# PSU.net
KiCad netlist of a schematic drawn in EAGLE
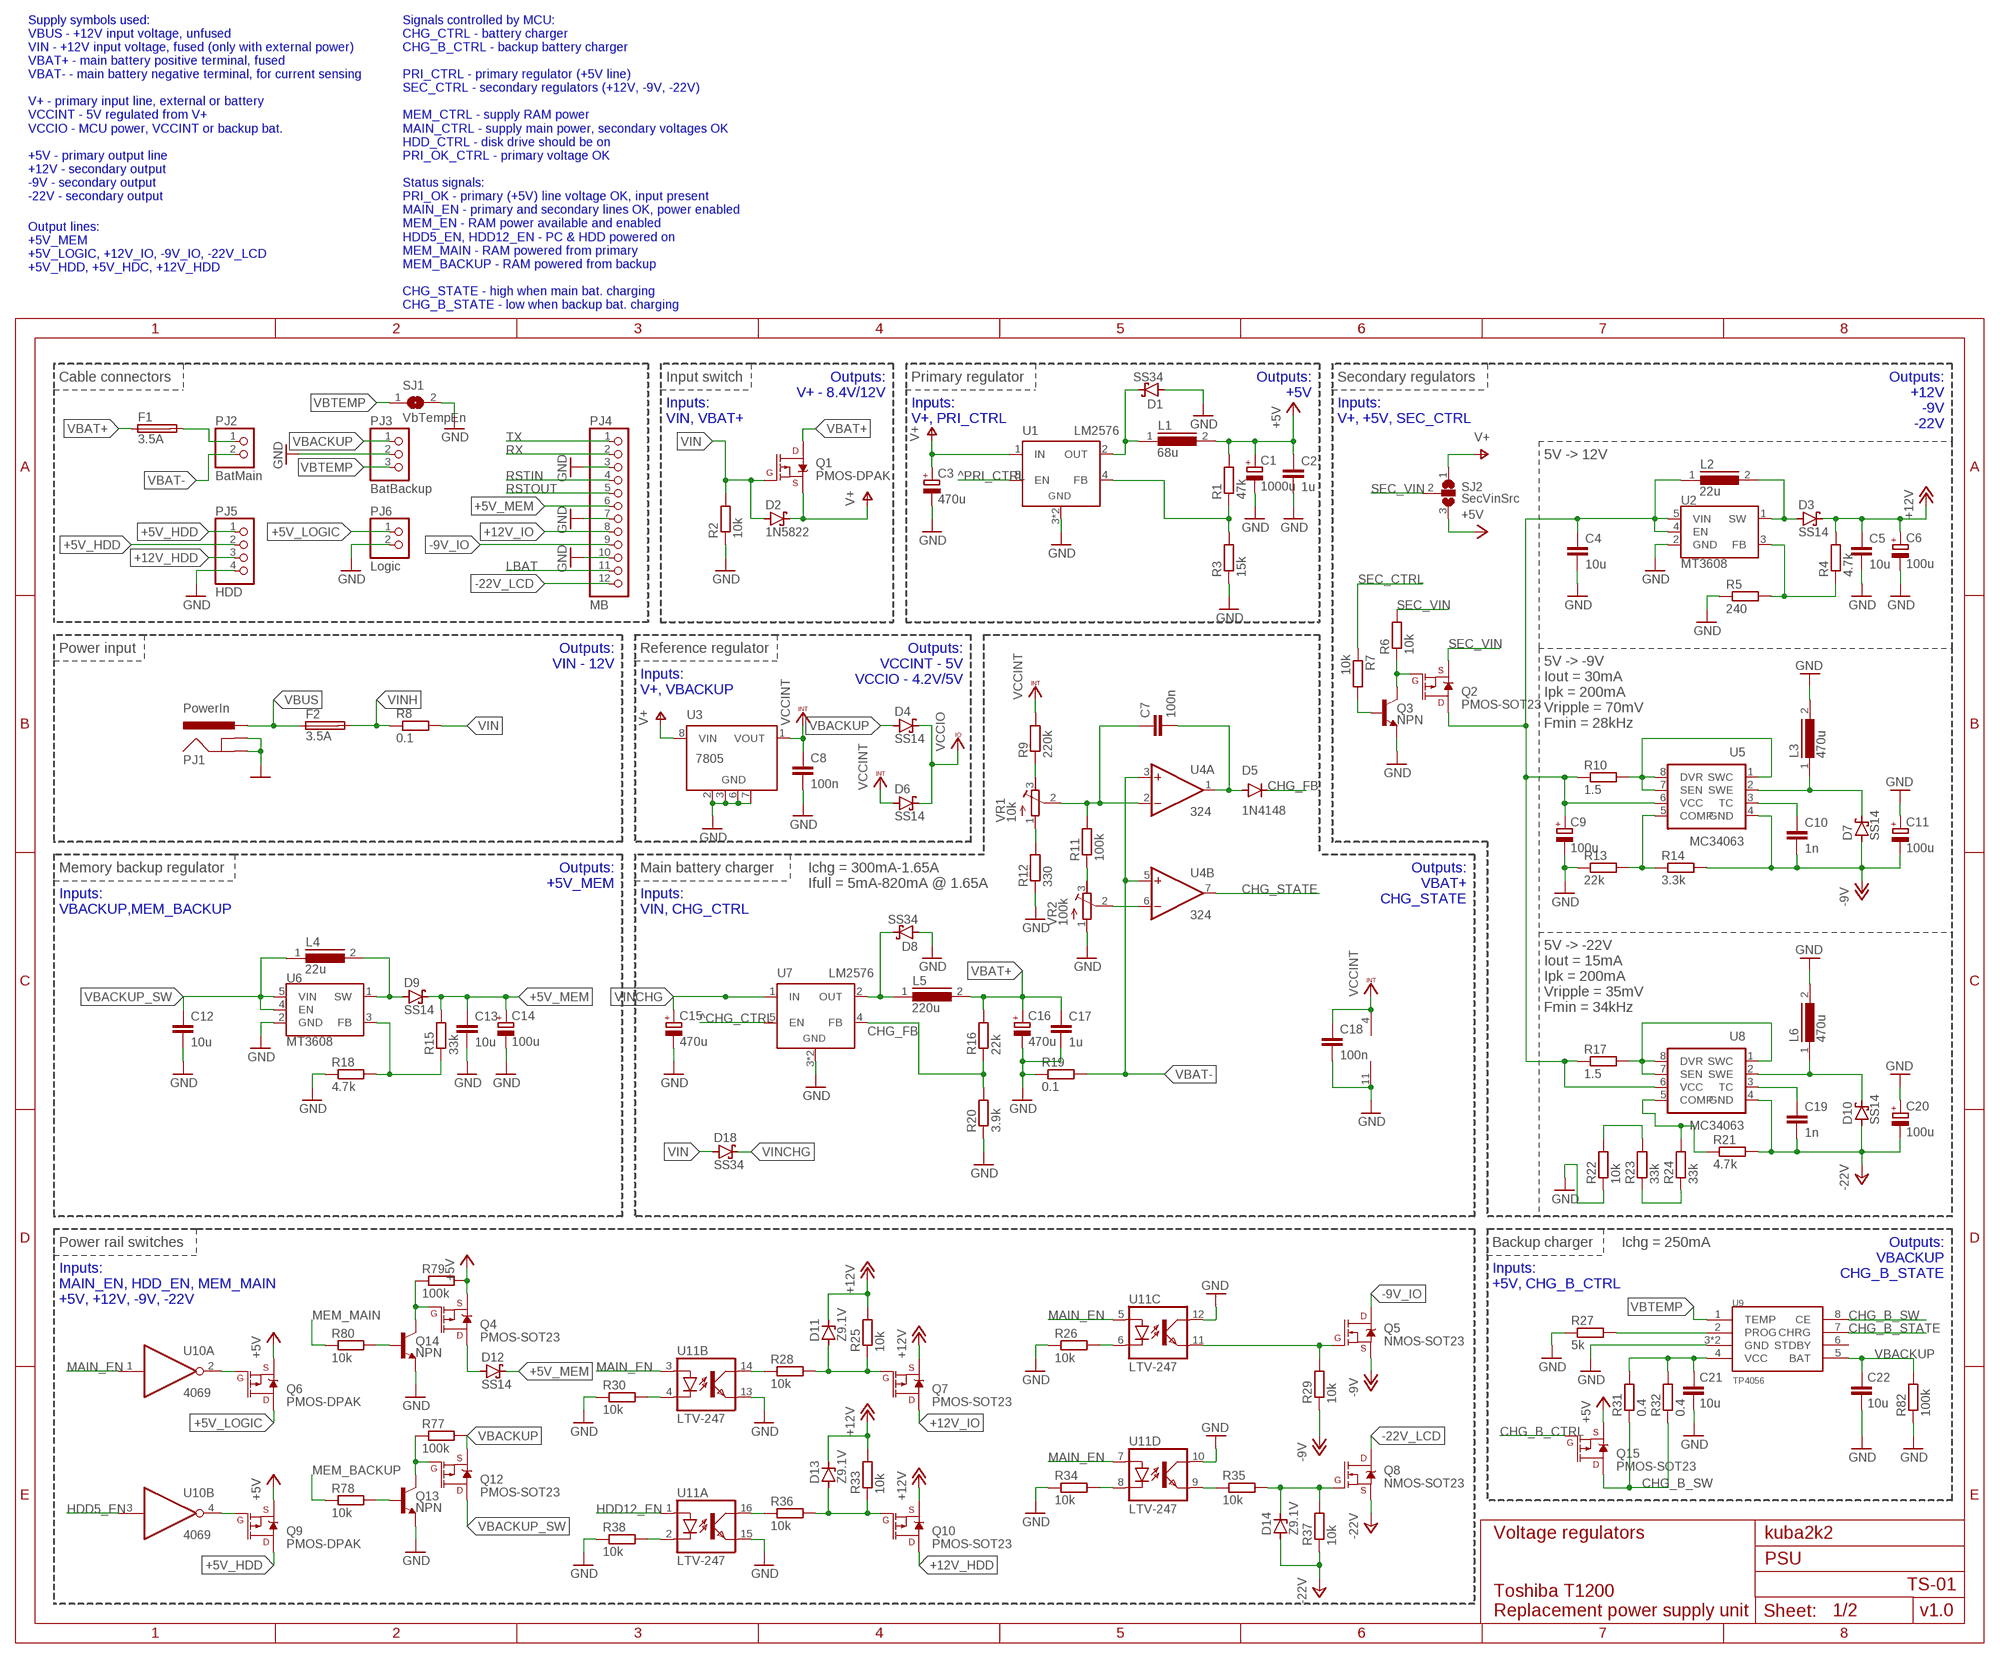
[diagram p0: schematic, sheet 1]
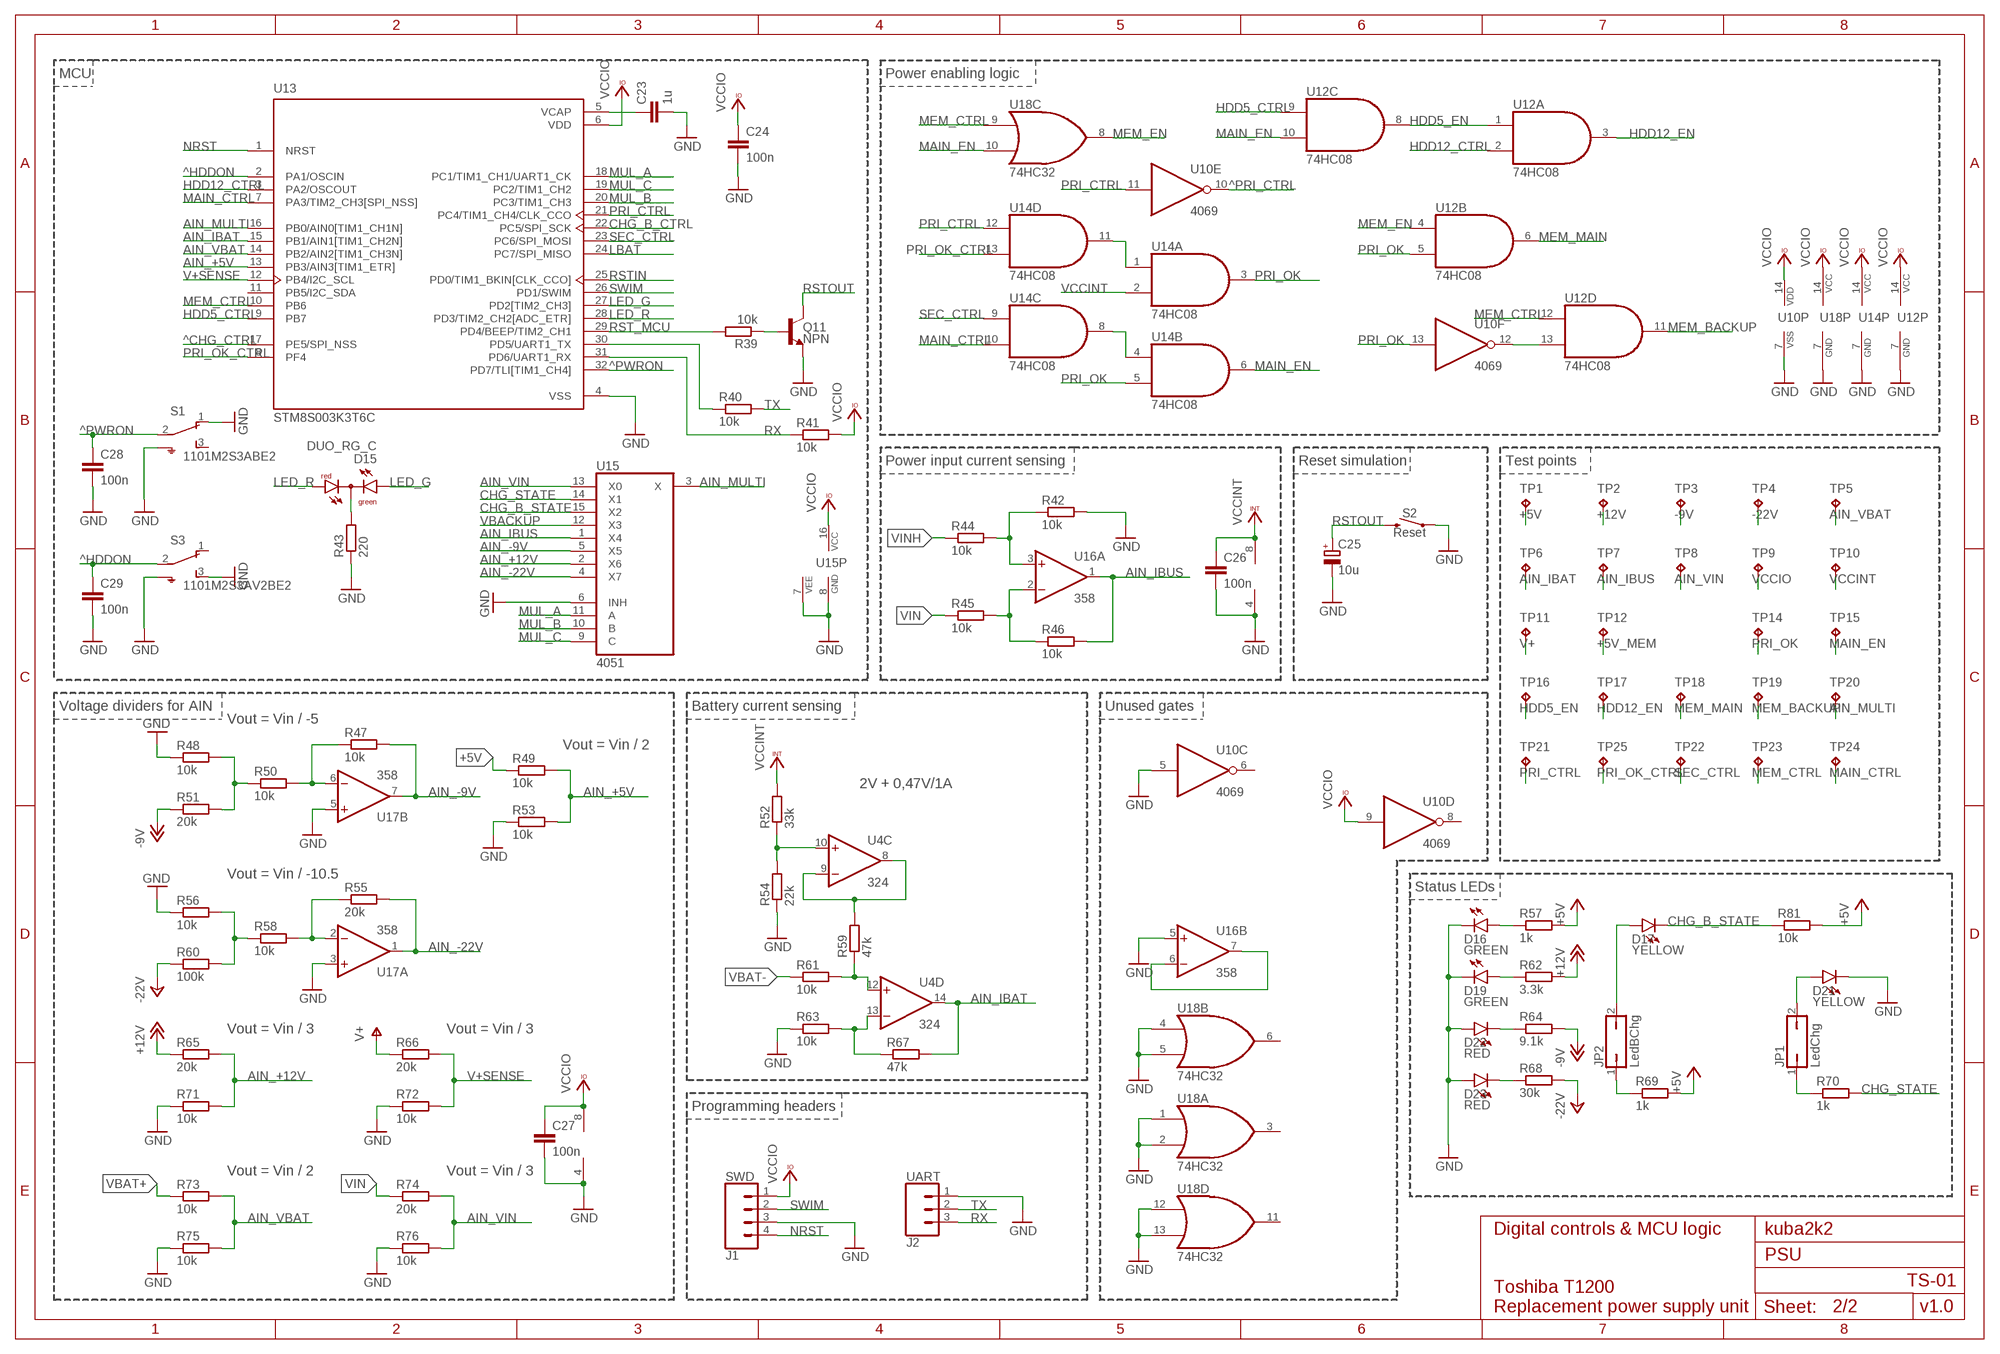
[diagram p1: schematic, sheet 2]

(export (version "E")
  (design (tool "Eeschema 10.0.6"))
  (components
    (comp (ref "C1")
      (value "1000u")
      (footprint "eagle-import:E5-10,5")
      (libsource (lib "eagle-import") (part "CPOL-EUE5-10.5"))
    )
    (comp (ref "C2")
      (value "1u")
      (footprint "eagle-import:C050-024X044")
      (libsource (lib "eagle-import") (part "C-EU050-024X044"))
    )
    (comp (ref "C3")
      (value "470u")
      (footprint "eagle-import:E3,5-8")
      (libsource (lib "eagle-import") (part "CPOL-EUE3.5-8"))
    )
    (comp (ref "C4")
      (value "10u")
      (footprint "eagle-import:C1206")
      (libsource (lib "eagle-import") (part "C-EUC1206"))
    )
    (comp (ref "C5")
      (value "10u")
      (footprint "eagle-import:C1206")
      (libsource (lib "eagle-import") (part "C-EUC1206"))
    )
    (comp (ref "C6")
      (value "100u")
      (footprint "eagle-import:E3,5-8")
      (libsource (lib "eagle-import") (part "CPOL-EUE3.5-8"))
    )
    (comp (ref "C7")
      (value "100n")
      (footprint "eagle-import:C0805")
      (libsource (lib "eagle-import") (part "C-EUC0805"))
    )
    (comp (ref "C8")
      (value "100n")
      (footprint "eagle-import:C0805")
      (libsource (lib "eagle-import") (part "C-EUC0805"))
    )
    (comp (ref "C9")
      (value "100u")
      (footprint "eagle-import:E3,5-8")
      (libsource (lib "eagle-import") (part "CPOL-EUE3.5-8"))
    )
    (comp (ref "C10")
      (value "1n")
      (footprint "eagle-import:C0805")
      (libsource (lib "eagle-import") (part "C-EUC0805"))
    )
    (comp (ref "C11")
      (value "100u")
      (footprint "eagle-import:E3,5-8")
      (libsource (lib "eagle-import") (part "CPOL-EUE3.5-8"))
    )
    (comp (ref "C12")
      (value "10u")
      (footprint "eagle-import:C1206")
      (libsource (lib "eagle-import") (part "C-EUC1206"))
    )
    (comp (ref "C13")
      (value "10u")
      (footprint "eagle-import:C1206")
      (libsource (lib "eagle-import") (part "C-EUC1206"))
    )
    (comp (ref "C14")
      (value "100u")
      (footprint "eagle-import:E3,5-8")
      (libsource (lib "eagle-import") (part "CPOL-EUE3.5-8"))
    )
    (comp (ref "C15")
      (value "470u")
      (footprint "eagle-import:E3,5-8")
      (libsource (lib "eagle-import") (part "CPOL-EUE3.5-8"))
    )
    (comp (ref "C16")
      (value "470u")
      (footprint "eagle-import:E3,5-8")
      (libsource (lib "eagle-import") (part "CPOL-EUE3.5-8"))
    )
    (comp (ref "C17")
      (value "1u")
      (footprint "eagle-import:C050-024X044")
      (libsource (lib "eagle-import") (part "C-EU050-024X044"))
    )
    (comp (ref "C18")
      (value "100n")
      (footprint "eagle-import:C0805")
      (libsource (lib "eagle-import") (part "C-EUC0805"))
    )
    (comp (ref "C19")
      (value "1n")
      (footprint "eagle-import:C0805")
      (libsource (lib "eagle-import") (part "C-EUC0805"))
    )
    (comp (ref "C20")
      (value "100u")
      (footprint "eagle-import:E3,5-8")
      (libsource (lib "eagle-import") (part "CPOL-EUE3.5-8"))
    )
    (comp (ref "C21")
      (value "10u")
      (footprint "eagle-import:C1206")
      (libsource (lib "eagle-import") (part "C-EUC1206"))
    )
    (comp (ref "C22")
      (value "10u")
      (footprint "eagle-import:C1206")
      (libsource (lib "eagle-import") (part "C-EUC1206"))
    )
    (comp (ref "D1")
      (value "SS34")
      (footprint "eagle-import:SMC")
      (libsource (lib "eagle-import") (part "SS34"))
    )
    (comp (ref "D2")
      (value "1N5822")
      (footprint "eagle-import:F126Z12")
      (libsource (lib "eagle-import") (part "SCHOTTKY-DIODEF126Z12"))
    )
    (comp (ref "D3")
      (value "SS14")
      (footprint "eagle-import:DO-214AC")
      (libsource (lib "eagle-import") (part "SS14"))
    )
    (comp (ref "D4")
      (value "SS14")
      (footprint "eagle-import:DO-214AC")
      (libsource (lib "eagle-import") (part "SS14"))
    )
    (comp (ref "D5")
      (value "1N4148")
      (footprint "eagle-import:DO35-7")
      (libsource (lib "eagle-import") (part "1N4148DO35-7"))
    )
    (comp (ref "D6")
      (value "SS14")
      (footprint "eagle-import:DO-214AC")
      (libsource (lib "eagle-import") (part "SS14"))
    )
    (comp (ref "D7")
      (value "SS14")
      (footprint "eagle-import:DO-214AC")
      (libsource (lib "eagle-import") (part "SS14"))
    )
    (comp (ref "D8")
      (value "SS34")
      (footprint "eagle-import:SMC")
      (libsource (lib "eagle-import") (part "SS34"))
    )
    (comp (ref "D9")
      (value "SS14")
      (footprint "eagle-import:DO-214AC")
      (libsource (lib "eagle-import") (part "SS14"))
    )
    (comp (ref "D10")
      (value "SS14")
      (footprint "eagle-import:DO-214AC")
      (libsource (lib "eagle-import") (part "SS14"))
    )
    (comp (ref "D11")
      (value "Z9.1V")
      (footprint "eagle-import:DO34Z7")
      (libsource (lib "eagle-import") (part "ZENER-DIODEDO34-7"))
    )
    (comp (ref "D12")
      (value "SS14")
      (footprint "eagle-import:DO-214AC")
      (libsource (lib "eagle-import") (part "SS14"))
    )
    (comp (ref "D13")
      (value "Z9.1V")
      (footprint "eagle-import:DO34Z7")
      (libsource (lib "eagle-import") (part "ZENER-DIODEDO34-7"))
    )
    (comp (ref "D14")
      (value "Z9.1V")
      (footprint "eagle-import:DO34Z7")
      (libsource (lib "eagle-import") (part "ZENER-DIODEDO34-7"))
    )
    (comp (ref "D18")
      (value "SS34")
      (footprint "eagle-import:SMC")
      (libsource (lib "eagle-import") (part "SS34"))
    )
    (comp (ref "F1")
      (value "3.5A")
      (footprint "eagle-import:2512")
      (libsource (lib "eagle-import") (part "FUSE-2512"))
    )
    (comp (ref "F2")
      (value "3.5A")
      (footprint "eagle-import:2512")
      (libsource (lib "eagle-import") (part "FUSE-2512"))
    )
    (comp (ref "L1")
      (value "68u")
      (footprint "eagle-import:SFT1030")
      (libsource (lib "eagle-import") (part "SFT1030"))
    )
    (comp (ref "L2")
      (value "22u")
      (footprint "eagle-import:DR127")
      (libsource (lib "eagle-import") (part "DR127"))
    )
    (comp (ref "L3")
      (value "470u")
      (footprint "eagle-import:COIL0608")
      (libsource (lib "eagle-import") (part "COIL0608"))
    )
    (comp (ref "L4")
      (value "22u")
      (footprint "eagle-import:DR127")
      (libsource (lib "eagle-import") (part "DR127"))
    )
    (comp (ref "L5")
      (value "220u")
      (footprint "eagle-import:SFT1030")
      (libsource (lib "eagle-import") (part "SFT1030"))
    )
    (comp (ref "L6")
      (value "470u")
      (footprint "eagle-import:COIL0608")
      (libsource (lib "eagle-import") (part "COIL0608"))
    )
    (comp (ref "PJ1")
      (value "PowerIn")
      (footprint "eagle-import:POWER_JACK_PTH")
      (libsource (lib "eagle-import") (part "POWER_JACK"))
    )
    (comp (ref "PJ2")
      (value "BatMain")
      (footprint "eagle-import:JST-PH2-4.00")
      (libsource (lib "eagle-import") (part "JST-PH2-4.00"))
    )
    (comp (ref "PJ3")
      (value "BatBackup")
      (footprint "eagle-import:JST-PH3")
      (libsource (lib "eagle-import") (part "JST-PH3"))
    )
    (comp (ref "PJ4")
      (value "MB")
      (footprint "eagle-import:JST-PH12")
      (libsource (lib "eagle-import") (part "JST-PH12"))
    )
    (comp (ref "PJ5")
      (value "HDD")
      (footprint "eagle-import:JST-PH4-2.54")
      (libsource (lib "eagle-import") (part "JST-PH4-2.54"))
    )
    (comp (ref "PJ6")
      (value "Logic")
      (footprint "eagle-import:JST-PH2-2.54")
      (libsource (lib "eagle-import") (part "JST-PH2-2.54"))
    )
    (comp (ref "Q1")
      (value "PMOS-DPAK")
      (footprint "eagle-import:TO-252_DPAK")
      (libsource (lib "eagle-import") (part "MOSFET_PCH-MCU20P10"))
    )
    (comp (ref "Q2")
      (value "PMOS-SOT23")
      (footprint "eagle-import:SOT23-3")
      (libsource (lib "eagle-import") (part "MOSFET_PCH-IRLML2244"))
    )
    (comp (ref "Q3")
      (value "NPN")
      (footprint "eagle-import:SOT23-3")
      (libsource (lib "eagle-import") (part "TRANS_NPN-MMBT2222AL"))
    )
    (comp (ref "Q4")
      (value "PMOS-SOT23")
      (footprint "eagle-import:SOT23-3")
      (libsource (lib "eagle-import") (part "MOSFET_PCH-IRLML2244"))
    )
    (comp (ref "Q5")
      (value "NMOS-SOT23")
      (footprint "eagle-import:SOT23-3")
      (libsource (lib "eagle-import") (part "MOSFET-NCH-AO3404A"))
    )
    (comp (ref "Q6")
      (value "PMOS-DPAK")
      (footprint "eagle-import:TO-252_DPAK")
      (libsource (lib "eagle-import") (part "MOSFET_PCH-MCU20P10"))
    )
    (comp (ref "Q7")
      (value "PMOS-SOT23")
      (footprint "eagle-import:SOT23-3")
      (libsource (lib "eagle-import") (part "MOSFET_PCH-IRLML2244"))
    )
    (comp (ref "Q8")
      (value "NMOS-SOT23")
      (footprint "eagle-import:SOT23-3")
      (libsource (lib "eagle-import") (part "MOSFET-NCH-AO3404A"))
    )
    (comp (ref "Q9")
      (value "PMOS-DPAK")
      (footprint "eagle-import:TO-252_DPAK")
      (libsource (lib "eagle-import") (part "MOSFET_PCH-MCU20P10"))
    )
    (comp (ref "Q10")
      (value "PMOS-SOT23")
      (footprint "eagle-import:SOT23-3")
      (libsource (lib "eagle-import") (part "MOSFET_PCH-IRLML2244"))
    )
    (comp (ref "Q12")
      (value "PMOS-SOT23")
      (footprint "eagle-import:SOT23-3")
      (libsource (lib "eagle-import") (part "MOSFET_PCH-IRLML2244"))
    )
    (comp (ref "Q13")
      (value "NPN")
      (footprint "eagle-import:SOT23-3")
      (libsource (lib "eagle-import") (part "TRANS_NPN-MMBT2222AL"))
    )
    (comp (ref "Q14")
      (value "NPN")
      (footprint "eagle-import:SOT23-3")
      (libsource (lib "eagle-import") (part "TRANS_NPN-MMBT2222AL"))
    )
    (comp (ref "Q15")
      (value "PMOS-SOT23")
      (footprint "eagle-import:SOT23-3")
      (libsource (lib "eagle-import") (part "MOSFET_PCH-IRLML2244"))
    )
    (comp (ref "R1")
      (value "47k")
      (footprint "eagle-import:R0805")
      (libsource (lib "eagle-import") (part "R-EU_R0805"))
    )
    (comp (ref "R2")
      (value "10k")
      (footprint "eagle-import:R0805")
      (libsource (lib "eagle-import") (part "R-EU_R0805"))
    )
    (comp (ref "R3")
      (value "15k")
      (footprint "eagle-import:R0805")
      (libsource (lib "eagle-import") (part "R-EU_R0805"))
    )
    (comp (ref "R4")
      (value "4.7k")
      (footprint "eagle-import:R0805")
      (libsource (lib "eagle-import") (part "R-EU_R0805"))
    )
    (comp (ref "R5")
      (value "240")
      (footprint "eagle-import:R0805")
      (libsource (lib "eagle-import") (part "R-EU_R0805"))
    )
    (comp (ref "R6")
      (value "10k")
      (footprint "eagle-import:R0805")
      (libsource (lib "eagle-import") (part "R-EU_R0805"))
    )
    (comp (ref "R7")
      (value "10k")
      (footprint "eagle-import:R0805")
      (libsource (lib "eagle-import") (part "R-EU_R0805"))
    )
    (comp (ref "R8")
      (value "0.1")
      (footprint "eagle-import:0411_15")
      (libsource (lib "eagle-import") (part "R-EU_0411/15"))
    )
    (comp (ref "R9")
      (value "220k")
      (footprint "eagle-import:R0805")
      (libsource (lib "eagle-import") (part "R-EU_R0805"))
    )
    (comp (ref "R10")
      (value "1.5")
      (footprint "eagle-import:0207_10")
      (libsource (lib "eagle-import") (part "R-EU_0207/10"))
    )
    (comp (ref "R11")
      (value "100k")
      (footprint "eagle-import:R0805")
      (libsource (lib "eagle-import") (part "R-EU_R0805"))
    )
    (comp (ref "R12")
      (value "330")
      (footprint "eagle-import:R0805")
      (libsource (lib "eagle-import") (part "R-EU_R0805"))
    )
    (comp (ref "R13")
      (value "22k")
      (footprint "eagle-import:R0805")
      (libsource (lib "eagle-import") (part "R-EU_R0805"))
    )
    (comp (ref "R14")
      (value "3.3k")
      (footprint "eagle-import:R0805")
      (libsource (lib "eagle-import") (part "R-EU_R0805"))
    )
    (comp (ref "R15")
      (value "33k")
      (footprint "eagle-import:R0805")
      (libsource (lib "eagle-import") (part "R-EU_R0805"))
    )
    (comp (ref "R16")
      (value "22k")
      (footprint "eagle-import:R0805")
      (libsource (lib "eagle-import") (part "R-EU_R0805"))
    )
    (comp (ref "R17")
      (value "1.5")
      (footprint "eagle-import:0207_10")
      (libsource (lib "eagle-import") (part "R-EU_0207/10"))
    )
    (comp (ref "R18")
      (value "4.7k")
      (footprint "eagle-import:R0805")
      (libsource (lib "eagle-import") (part "R-EU_R0805"))
    )
    (comp (ref "R19")
      (value "0.1")
      (footprint "eagle-import:0411_15")
      (libsource (lib "eagle-import") (part "R-EU_0411/15"))
    )
    (comp (ref "R20")
      (value "3.9k")
      (footprint "eagle-import:R0805")
      (libsource (lib "eagle-import") (part "R-EU_R0805"))
    )
    (comp (ref "R21")
      (value "4.7k")
      (footprint "eagle-import:R0805")
      (libsource (lib "eagle-import") (part "R-EU_R0805"))
    )
    (comp (ref "R22")
      (value "10k")
      (footprint "eagle-import:R0805")
      (libsource (lib "eagle-import") (part "R-EU_R0805"))
    )
    (comp (ref "R23")
      (value "33k")
      (footprint "eagle-import:R0805")
      (libsource (lib "eagle-import") (part "R-EU_R0805"))
    )
    (comp (ref "R24")
      (value "33k")
      (footprint "eagle-import:R0805")
      (libsource (lib "eagle-import") (part "R-EU_R0805"))
    )
    (comp (ref "R25")
      (value "10k")
      (footprint "eagle-import:R0805")
      (libsource (lib "eagle-import") (part "R-EU_R0805"))
    )
    (comp (ref "R26")
      (value "10k")
      (footprint "eagle-import:R0805")
      (libsource (lib "eagle-import") (part "R-EU_R0805"))
    )
    (comp (ref "R27")
      (value "5k")
      (footprint "eagle-import:R0805")
      (libsource (lib "eagle-import") (part "R-EU_R0805"))
    )
    (comp (ref "R28")
      (value "10k")
      (footprint "eagle-import:R0805")
      (libsource (lib "eagle-import") (part "R-EU_R0805"))
    )
    (comp (ref "R29")
      (value "10k")
      (footprint "eagle-import:R0805")
      (libsource (lib "eagle-import") (part "R-EU_R0805"))
    )
    (comp (ref "R30")
      (value "10k")
      (footprint "eagle-import:R0805")
      (libsource (lib "eagle-import") (part "R-EU_R0805"))
    )
    (comp (ref "R31")
      (value "0.4")
      (footprint "eagle-import:0207_10")
      (libsource (lib "eagle-import") (part "R-EU_0207/10"))
    )
    (comp (ref "R32")
      (value "0.4")
      (footprint "eagle-import:R1206")
      (libsource (lib "eagle-import") (part "R-EU_R1206"))
    )
    (comp (ref "R33")
      (value "10k")
      (footprint "eagle-import:R0805")
      (libsource (lib "eagle-import") (part "R-EU_R0805"))
    )
    (comp (ref "R34")
      (value "10k")
      (footprint "eagle-import:R0805")
      (libsource (lib "eagle-import") (part "R-EU_R0805"))
    )
    (comp (ref "R35")
      (value "10k")
      (footprint "eagle-import:R0805")
      (libsource (lib "eagle-import") (part "R-EU_R0805"))
    )
    (comp (ref "R36")
      (value "10k")
      (footprint "eagle-import:R0805")
      (libsource (lib "eagle-import") (part "R-EU_R0805"))
    )
    (comp (ref "R37")
      (value "10k")
      (footprint "eagle-import:R0805")
      (libsource (lib "eagle-import") (part "R-EU_R0805"))
    )
    (comp (ref "R38")
      (value "10k")
      (footprint "eagle-import:R0805")
      (libsource (lib "eagle-import") (part "R-EU_R0805"))
    )
    (comp (ref "R77")
      (value "100k")
      (footprint "eagle-import:R0805")
      (libsource (lib "eagle-import") (part "R-EU_R0805"))
    )
    (comp (ref "R78")
      (value "10k")
      (footprint "eagle-import:R0805")
      (libsource (lib "eagle-import") (part "R-EU_R0805"))
    )
    (comp (ref "R79")
      (value "100k")
      (footprint "eagle-import:R0805")
      (libsource (lib "eagle-import") (part "R-EU_R0805"))
    )
    (comp (ref "R80")
      (value "10k")
      (footprint "eagle-import:R0805")
      (libsource (lib "eagle-import") (part "R-EU_R0805"))
    )
    (comp (ref "R82")
      (value "100k")
      (footprint "eagle-import:R0805")
      (libsource (lib "eagle-import") (part "R-EU_R0805"))
    )
    (comp (ref "SJ1")
      (value "VbTempEn")
      (footprint "eagle-import:SJ")
      (libsource (lib "eagle-import") (part "SJ"))
    )
    (comp (ref "SJ2")
      (value "SecVinSrc")
      (footprint "eagle-import:SJ_2")
      (libsource (lib "eagle-import") (part "SJ2W"))
    )
    (comp (ref "U1")
      (value "LM2576")
      (footprint "eagle-import:TO220-52-VIAHOLE")
      (fields (field (name "SPICEPREFIX") "X"))
      (libsource (lib "eagle-import") (part "LM2596TH-VIAHOLE"))
    )
    (comp (ref "U2")
      (value "MT3608")
      (footprint "eagle-import:SOT23-6")
      (fields (field (name "SPICEPREFIX") "X"))
      (libsource (lib "eagle-import") (part "MT3608"))
    )
    (comp (ref "U3")
      (value "7805")
      (footprint "eagle-import:SO08")
      (libsource (lib "eagle-import") (part "78LSMD05"))
    )
    (comp (ref "U4")
      (value "324")
      (footprint "eagle-import:SO14")
      (libsource (lib "eagle-import") (part "LM324D"))
    )
    (comp (ref "U5")
      (value "MC34063")
      (footprint "eagle-import:SO08")
      (libsource (lib "eagle-import") (part "MC34063SMD"))
    )
    (comp (ref "U6")
      (value "MT3608")
      (footprint "eagle-import:SOT23-6")
      (libsource (lib "eagle-import") (part "MT3608"))
    )
    (comp (ref "U7")
      (value "LM2576")
      (footprint "eagle-import:TO220-52-VIAHOLE")
      (libsource (lib "eagle-import") (part "LM2596TH-VIAHOLE"))
    )
    (comp (ref "U8")
      (value "MC34063")
      (footprint "eagle-import:SO08")
      (libsource (lib "eagle-import") (part "MC34063SMD"))
    )
    (comp (ref "U9")
      (value "TP4056")
      (footprint "eagle-import:SO08-PAD")
      (libsource (lib "eagle-import") (part "TP4056"))
    )
    (comp (ref "U10")
      (value "4069")
      (footprint "eagle-import:SO14")
      (libsource (lib "eagle-import") (part "4069D"))
    )
    (comp (ref "U11")
      (value "LTV-247")
      (footprint "eagle-import:SO16-GULLWING")
      (libsource (lib "eagle-import") (part "LTV-247"))
    )
    (comp (ref "VR1")
      (value "10k")
      (footprint "eagle-import:RTRIM3296W")
      (libsource (lib "eagle-import") (part "R-TRIMM3296W"))
    )
    (comp (ref "VR2")
      (value "100k")
      (footprint "eagle-import:RTRIM3296W")
      (libsource (lib "eagle-import") (part "R-TRIMM3296W"))
    )
    (comp (ref "C23")
      (value "1u")
      (footprint "eagle-import:C050-024X044")
      (libsource (lib "eagle-import") (part "C-EU050-024X044"))
    )
    (comp (ref "C24")
      (value "100n")
      (footprint "eagle-import:C0805")
      (libsource (lib "eagle-import") (part "C-EUC0805"))
    )
    (comp (ref "C25")
      (value "10u")
      (footprint "eagle-import:E2-5")
      (libsource (lib "eagle-import") (part "CPOL-EUE2-5"))
    )
    (comp (ref "C26")
      (value "100n")
      (footprint "eagle-import:C0805")
      (libsource (lib "eagle-import") (part "C-EUC0805"))
    )
    (comp (ref "C27")
      (value "100n")
      (footprint "eagle-import:C0805")
      (libsource (lib "eagle-import") (part "C-EUC0805"))
    )
    (comp (ref "C28")
      (value "100n")
      (footprint "eagle-import:C0805")
      (libsource (lib "eagle-import") (part "C-EUC0805"))
    )
    (comp (ref "C29")
      (value "100n")
      (footprint "eagle-import:C0805")
      (libsource (lib "eagle-import") (part "C-EUC0805"))
    )
    (comp (ref "D15")
      (value "DUO_RG_C")
      (footprint "eagle-import:DUOLED-C-5MM")
      (libsource (lib "eagle-import") (part "DUOLED-RG-C"))
    )
    (comp (ref "D16")
      (value "GREEN")
      (footprint "eagle-import:CHIP-LED0805")
      (libsource (lib "eagle-import") (part "LEDCHIP-LED0805"))
    )
    (comp (ref "D17")
      (value "YELLOW")
      (footprint "eagle-import:CHIP-LED0805")
      (libsource (lib "eagle-import") (part "LEDCHIP-LED0805"))
    )
    (comp (ref "D19")
      (value "GREEN")
      (footprint "eagle-import:CHIP-LED0805")
      (libsource (lib "eagle-import") (part "LEDCHIP-LED0805"))
    )
    (comp (ref "D21")
      (value "YELLOW")
      (footprint "eagle-import:CHIP-LED0805")
      (libsource (lib "eagle-import") (part "LEDCHIP-LED0805"))
    )
    (comp (ref "D22")
      (value "RED")
      (footprint "eagle-import:CHIP-LED0805")
      (libsource (lib "eagle-import") (part "LEDCHIP-LED0805"))
    )
    (comp (ref "D23")
      (value "RED")
      (footprint "eagle-import:CHIP-LED0805")
      (libsource (lib "eagle-import") (part "LEDCHIP-LED0805"))
    )
    (comp (ref "J1")
      (value "SWD")
      (footprint "eagle-import:1X04")
      (libsource (lib "eagle-import") (part "CONN_04PTH"))
    )
    (comp (ref "J2")
      (value "UART")
      (footprint "eagle-import:1X03")
      (libsource (lib "eagle-import") (part "CONN_03"))
    )
    (comp (ref "JP1")
      (value "LedChg")
      (footprint "eagle-import:JP1")
      (libsource (lib "eagle-import") (part "JP1Q"))
    )
    (comp (ref "JP2")
      (value "LedBChg")
      (footprint "eagle-import:JP1")
      (libsource (lib "eagle-import") (part "JP1Q"))
    )
    (comp (ref "Q11")
      (value "NPN")
      (footprint "eagle-import:SOT23-3")
      (libsource (lib "eagle-import") (part "TRANS_NPN-MMBT2222AL"))
    )
    (comp (ref "R39")
      (value "10k")
      (footprint "eagle-import:R0805")
      (libsource (lib "eagle-import") (part "R-EU_R0805"))
    )
    (comp (ref "R40")
      (value "10k")
      (footprint "eagle-import:R0805")
      (libsource (lib "eagle-import") (part "R-EU_R0805"))
    )
    (comp (ref "R41")
      (value "10k")
      (footprint "eagle-import:R0805")
      (libsource (lib "eagle-import") (part "R-EU_R0805"))
    )
    (comp (ref "R42")
      (value "10k")
      (footprint "eagle-import:R0805")
      (libsource (lib "eagle-import") (part "R-EU_R0805"))
    )
    (comp (ref "R43")
      (value "220")
      (footprint "eagle-import:R0805")
      (libsource (lib "eagle-import") (part "R-EU_R0805"))
    )
    (comp (ref "R44")
      (value "10k")
      (footprint "eagle-import:R0805")
      (libsource (lib "eagle-import") (part "R-EU_R0805"))
    )
    (comp (ref "R45")
      (value "10k")
      (footprint "eagle-import:R0805")
      (libsource (lib "eagle-import") (part "R-EU_R0805"))
    )
    (comp (ref "R46")
      (value "10k")
      (footprint "eagle-import:R0805")
      (libsource (lib "eagle-import") (part "R-EU_R0805"))
    )
    (comp (ref "R47")
      (value "10k")
      (footprint "eagle-import:R0805")
      (libsource (lib "eagle-import") (part "R-EU_R0805"))
    )
    (comp (ref "R48")
      (value "10k")
      (footprint "eagle-import:R0805")
      (libsource (lib "eagle-import") (part "R-EU_R0805"))
    )
    (comp (ref "R49")
      (value "10k")
      (footprint "eagle-import:R0805")
      (libsource (lib "eagle-import") (part "R-EU_R0805"))
    )
    (comp (ref "R50")
      (value "10k")
      (footprint "eagle-import:R0805")
      (libsource (lib "eagle-import") (part "R-EU_R0805"))
    )
    (comp (ref "R51")
      (value "20k")
      (footprint "eagle-import:R0805")
      (libsource (lib "eagle-import") (part "R-EU_R0805"))
    )
    (comp (ref "R52")
      (value "33k")
      (footprint "eagle-import:R0805")
      (libsource (lib "eagle-import") (part "R-EU_R0805"))
    )
    (comp (ref "R53")
      (value "10k")
      (footprint "eagle-import:R0805")
      (libsource (lib "eagle-import") (part "R-EU_R0805"))
    )
    (comp (ref "R54")
      (value "22k")
      (footprint "eagle-import:R0805")
      (libsource (lib "eagle-import") (part "R-EU_R0805"))
    )
    (comp (ref "R55")
      (value "20k")
      (footprint "eagle-import:R0805")
      (libsource (lib "eagle-import") (part "R-EU_R0805"))
    )
    (comp (ref "R56")
      (value "10k")
      (footprint "eagle-import:R0805")
      (libsource (lib "eagle-import") (part "R-EU_R0805"))
    )
    (comp (ref "R57")
      (value "1k")
      (footprint "eagle-import:R0805")
      (libsource (lib "eagle-import") (part "R-EU_R0805"))
    )
    (comp (ref "R58")
      (value "10k")
      (footprint "eagle-import:R0805")
      (libsource (lib "eagle-import") (part "R-EU_R0805"))
    )
    (comp (ref "R59")
      (value "47k")
      (footprint "eagle-import:R0805")
      (libsource (lib "eagle-import") (part "R-EU_R0805"))
    )
    (comp (ref "R60")
      (value "100k")
      (footprint "eagle-import:R0805")
      (libsource (lib "eagle-import") (part "R-EU_R0805"))
    )
    (comp (ref "R61")
      (value "10k")
      (footprint "eagle-import:R0805")
      (libsource (lib "eagle-import") (part "R-EU_R0805"))
    )
    (comp (ref "R62")
      (value "3.3k")
      (footprint "eagle-import:R0805")
      (libsource (lib "eagle-import") (part "R-EU_R0805"))
    )
    (comp (ref "R63")
      (value "10k")
      (footprint "eagle-import:R0805")
      (libsource (lib "eagle-import") (part "R-EU_R0805"))
    )
    (comp (ref "R64")
      (value "9.1k")
      (footprint "eagle-import:R0805")
      (libsource (lib "eagle-import") (part "R-EU_R0805"))
    )
    (comp (ref "R65")
      (value "20k")
      (footprint "eagle-import:R0805")
      (libsource (lib "eagle-import") (part "R-EU_R0805"))
    )
    (comp (ref "R66")
      (value "20k")
      (footprint "eagle-import:R0805")
      (libsource (lib "eagle-import") (part "R-EU_R0805"))
    )
    (comp (ref "R67")
      (value "47k")
      (footprint "eagle-import:R0805")
      (libsource (lib "eagle-import") (part "R-EU_R0805"))
    )
    (comp (ref "R68")
      (value "30k")
      (footprint "eagle-import:R0805")
      (libsource (lib "eagle-import") (part "R-EU_R0805"))
    )
    (comp (ref "R69")
      (value "1k")
      (footprint "eagle-import:R0805")
      (libsource (lib "eagle-import") (part "R-EU_R0805"))
    )
    (comp (ref "R70")
      (value "1k")
      (footprint "eagle-import:R0805")
      (libsource (lib "eagle-import") (part "R-EU_R0805"))
    )
    (comp (ref "R71")
      (value "10k")
      (footprint "eagle-import:R0805")
      (libsource (lib "eagle-import") (part "R-EU_R0805"))
    )
    (comp (ref "R72")
      (value "10k")
      (footprint "eagle-import:R0805")
      (libsource (lib "eagle-import") (part "R-EU_R0805"))
    )
    (comp (ref "R73")
      (value "10k")
      (footprint "eagle-import:R0805")
      (libsource (lib "eagle-import") (part "R-EU_R0805"))
    )
    (comp (ref "R74")
      (value "20k")
      (footprint "eagle-import:R0805")
      (libsource (lib "eagle-import") (part "R-EU_R0805"))
    )
    (comp (ref "R75")
      (value "10k")
      (footprint "eagle-import:R0805")
      (libsource (lib "eagle-import") (part "R-EU_R0805"))
    )
    (comp (ref "R76")
      (value "10k")
      (footprint "eagle-import:R0805")
      (libsource (lib "eagle-import") (part "R-EU_R0805"))
    )
    (comp (ref "R81")
      (value "10k")
      (footprint "eagle-import:R0805")
      (libsource (lib "eagle-import") (part "R-EU_R0805"))
    )
    (comp (ref "S1")
      (value "1101M2S3ABE2")
      (footprint "eagle-import:1101M2S3ABE2")
      (libsource (lib "eagle-import") (part "1101M2S3ABE2"))
    )
    (comp (ref "S2")
      (value "Reset")
      (footprint "eagle-import:TACTILE_SWITCH_SMD_6.2MM_TALL")
      (libsource (lib "eagle-import") (part "MOMENTARY-SWITCH-SPST-SMD-6.2MM-TALL"))
    )
    (comp (ref "S3")
      (value "1101M2S3AV2BE2")
      (footprint "eagle-import:1101M2S3AV2BE2")
      (libsource (lib "eagle-import") (part "1101M2S3AV2BE2"))
    )
    (comp (ref "TP1")
      (value "TPB1,27")
      (footprint "eagle-import:B1,27")
      (libsource (lib "eagle-import") (part "TPB1,27"))
    )
    (comp (ref "TP2")
      (value "TPB1,27")
      (footprint "eagle-import:B1,27")
      (libsource (lib "eagle-import") (part "TPB1,27"))
    )
    (comp (ref "TP3")
      (value "TPB1,27")
      (footprint "eagle-import:B1,27")
      (libsource (lib "eagle-import") (part "TPB1,27"))
    )
    (comp (ref "TP4")
      (value "TPB1,27")
      (footprint "eagle-import:B1,27")
      (libsource (lib "eagle-import") (part "TPB1,27"))
    )
    (comp (ref "TP5")
      (value "TPB1,27")
      (footprint "eagle-import:B1,27")
      (libsource (lib "eagle-import") (part "TPB1,27"))
    )
    (comp (ref "TP6")
      (value "TPB1,27")
      (footprint "eagle-import:B1,27")
      (libsource (lib "eagle-import") (part "TPB1,27"))
    )
    (comp (ref "TP7")
      (value "TPB1,27")
      (footprint "eagle-import:B1,27")
      (libsource (lib "eagle-import") (part "TPB1,27"))
    )
    (comp (ref "TP8")
      (value "TPB1,27")
      (footprint "eagle-import:B1,27")
      (libsource (lib "eagle-import") (part "TPB1,27"))
    )
    (comp (ref "TP9")
      (value "TPB1,27")
      (footprint "eagle-import:B1,27")
      (libsource (lib "eagle-import") (part "TPB1,27"))
    )
    (comp (ref "TP10")
      (value "TPB1,27")
      (footprint "eagle-import:B1,27")
      (libsource (lib "eagle-import") (part "TPB1,27"))
    )
    (comp (ref "TP11")
      (value "TPB1,27")
      (footprint "eagle-import:B1,27")
      (libsource (lib "eagle-import") (part "TPB1,27"))
    )
    (comp (ref "TP12")
      (value "TPB1,27")
      (footprint "eagle-import:B1,27")
      (libsource (lib "eagle-import") (part "TPB1,27"))
    )
    (comp (ref "TP14")
      (value "TPB1,27")
      (footprint "eagle-import:B1,27")
      (libsource (lib "eagle-import") (part "TPB1,27"))
    )
    (comp (ref "TP15")
      (value "TPB1,27")
      (footprint "eagle-import:B1,27")
      (libsource (lib "eagle-import") (part "TPB1,27"))
    )
    (comp (ref "TP16")
      (value "TPB1,27")
      (footprint "eagle-import:B1,27")
      (libsource (lib "eagle-import") (part "TPB1,27"))
    )
    (comp (ref "TP17")
      (value "TPB1,27")
      (footprint "eagle-import:B1,27")
      (libsource (lib "eagle-import") (part "TPB1,27"))
    )
    (comp (ref "TP18")
      (value "TPB1,27")
      (footprint "eagle-import:B1,27")
      (libsource (lib "eagle-import") (part "TPB1,27"))
    )
    (comp (ref "TP19")
      (value "TPB1,27")
      (footprint "eagle-import:B1,27")
      (libsource (lib "eagle-import") (part "TPB1,27"))
    )
    (comp (ref "TP20")
      (value "TPB1,27")
      (footprint "eagle-import:B1,27")
      (libsource (lib "eagle-import") (part "TPB1,27"))
    )
    (comp (ref "TP21")
      (value "TPB1,27")
      (footprint "eagle-import:B1,27")
      (libsource (lib "eagle-import") (part "TPB1,27"))
    )
    (comp (ref "TP22")
      (value "TPB1,27")
      (footprint "eagle-import:B1,27")
      (libsource (lib "eagle-import") (part "TPB1,27"))
    )
    (comp (ref "TP23")
      (value "TPB1,27")
      (footprint "eagle-import:B1,27")
      (libsource (lib "eagle-import") (part "TPB1,27"))
    )
    (comp (ref "TP24")
      (value "TPB1,27")
      (footprint "eagle-import:B1,27")
      (libsource (lib "eagle-import") (part "TPB1,27"))
    )
    (comp (ref "TP25")
      (value "TPB1,27")
      (footprint "eagle-import:B1,27")
      (libsource (lib "eagle-import") (part "TPB1,27"))
    )
    (comp (ref "U12")
      (value "74HC08")
      (footprint "eagle-import:SO14")
      (libsource (lib "eagle-import") (part "7408DLS"))
    )
    (comp (ref "U13")
      (value "STM8S003K3T6C")
      (footprint "eagle-import:QFP80P900X900X160-32N")
      (fields (field (name "MF") "STMicroelectronics"))
      (libsource (lib "eagle-import") (part "STM8S003K3T6C"))
    )
    (comp (ref "U14")
      (value "74HC08")
      (footprint "eagle-import:SO14")
      (libsource (lib "eagle-import") (part "7408DLS"))
    )
    (comp (ref "U15")
      (value "4051")
      (footprint "eagle-import:SO16")
      (libsource (lib "eagle-import") (part "4051D"))
    )
    (comp (ref "U16")
      (value "358")
      (footprint "eagle-import:SO08")
      (libsource (lib "eagle-import") (part "LM358D"))
    )
    (comp (ref "U17")
      (value "358")
      (footprint "eagle-import:SO08")
      (libsource (lib "eagle-import") (part "LM358D"))
    )
    (comp (ref "U18")
      (value "74HC32")
      (footprint "eagle-import:SO14")
      (libsource (lib "eagle-import") (part "7432D"))
    )
  )
  (nets
    (net (code "1") (name "+5V") (class "Default")
      (node (ref "C1") (pin "+") (pinfunction "+_+") (pintype "passive"))
      (node (ref "C2") (pin "1") (pinfunction "1_1") (pintype "passive"))
      (node (ref "L1") (pin "2") (pinfunction "2_2") (pintype "passive"))
      (node (ref "Q15") (pin "2") (pinfunction "S_2") (pintype "bidirectional"))
      (node (ref "Q4") (pin "2") (pinfunction "S_2") (pintype "bidirectional"))
      (node (ref "Q6") (pin "3") (pinfunction "S_3") (pintype "bidirectional"))
      (node (ref "Q9") (pin "3") (pinfunction "S_3") (pintype "bidirectional"))
      (node (ref "R1") (pin "2") (pinfunction "2_2") (pintype "passive"))
      (node (ref "R49") (pin "1") (pinfunction "1_1") (pintype "passive"))
      (node (ref "R57") (pin "2") (pinfunction "2_2") (pintype "passive"))
      (node (ref "R69") (pin "2") (pinfunction "2_2") (pintype "passive"))
      (node (ref "R79") (pin "2") (pinfunction "2_2") (pintype "passive"))
      (node (ref "R81") (pin "2") (pinfunction "2_2") (pintype "passive"))
      (node (ref "SJ2") (pin "3") (pinfunction "3_3") (pintype "passive"))
      (node (ref "TP1") (pin "TP") (pinfunction "TP_TP") (pintype "input"))
    )
    (net (code "2") (name "+5V_HDD") (class "Default")
      (node (ref "PJ5") (pin "1") (pinfunction "1_1") (pintype "passive"))
      (node (ref "PJ5") (pin "2") (pinfunction "2_2") (pintype "passive"))
      (node (ref "Q9") (pin "2") (pinfunction "D_2") (pintype "bidirectional"))
    )
    (net (code "3") (name "+5V_LOGIC") (class "Default")
      (node (ref "PJ6") (pin "1") (pinfunction "1_1") (pintype "passive"))
      (node (ref "Q6") (pin "2") (pinfunction "D_2") (pintype "bidirectional"))
    )
    (net (code "4") (name "+5V_MEM") (class "Default")
      (node (ref "C13") (pin "1") (pinfunction "1_1") (pintype "passive"))
      (node (ref "C14") (pin "+") (pinfunction "+_+") (pintype "passive"))
      (node (ref "D12") (pin "C") (pinfunction "C_C") (pintype "passive"))
      (node (ref "D9") (pin "C") (pinfunction "C_C") (pintype "passive"))
      (node (ref "PJ4") (pin "6") (pinfunction "6_6") (pintype "passive"))
      (node (ref "R15") (pin "2") (pinfunction "2_2") (pintype "passive"))
      (node (ref "TP12") (pin "TP") (pinfunction "TP_TP") (pintype "input"))
    )
    (net (code "5") (name "+12V") (class "Default")
      (node (ref "C5") (pin "1") (pinfunction "1_1") (pintype "passive"))
      (node (ref "C6") (pin "+") (pinfunction "+_+") (pintype "passive"))
      (node (ref "D11") (pin "C") (pinfunction "C_C") (pintype "passive"))
      (node (ref "D13") (pin "C") (pinfunction "C_C") (pintype "passive"))
      (node (ref "D3") (pin "C") (pinfunction "C_C") (pintype "passive"))
      (node (ref "Q10") (pin "2") (pinfunction "S_2") (pintype "bidirectional"))
      (node (ref "Q7") (pin "2") (pinfunction "S_2") (pintype "bidirectional"))
      (node (ref "R25") (pin "2") (pinfunction "2_2") (pintype "passive"))
      (node (ref "R33") (pin "2") (pinfunction "2_2") (pintype "passive"))
      (node (ref "R4") (pin "2") (pinfunction "2_2") (pintype "passive"))
      (node (ref "R62") (pin "2") (pinfunction "2_2") (pintype "passive"))
      (node (ref "R65") (pin "1") (pinfunction "1_1") (pintype "passive"))
      (node (ref "TP2") (pin "TP") (pinfunction "TP_TP") (pintype "input"))
    )
    (net (code "6") (name "+12V_HDD") (class "Default")
      (node (ref "PJ5") (pin "3") (pinfunction "3_3") (pintype "passive"))
      (node (ref "Q10") (pin "3") (pinfunction "D_3") (pintype "bidirectional"))
    )
    (net (code "7") (name "+12V_IO") (class "Default")
      (node (ref "PJ4") (pin "8") (pinfunction "8_8") (pintype "passive"))
      (node (ref "Q7") (pin "3") (pinfunction "D_3") (pintype "bidirectional"))
    )
    (net (code "8") (name "-9V") (class "Default")
      (node (ref "C10") (pin "2") (pinfunction "2_2") (pintype "passive"))
      (node (ref "C11") (pin "-") (pinfunction "-_-") (pintype "passive"))
      (node (ref "D7") (pin "A") (pinfunction "A_A") (pintype "passive"))
      (node (ref "Q5") (pin "2") (pinfunction "S_2") (pintype "bidirectional"))
      (node (ref "R14") (pin "2") (pinfunction "2_2") (pintype "passive"))
      (node (ref "R29") (pin "1") (pinfunction "1_1") (pintype "passive"))
      (node (ref "R51") (pin "1") (pinfunction "1_1") (pintype "passive"))
      (node (ref "R64") (pin "2") (pinfunction "2_2") (pintype "passive"))
      (node (ref "TP3") (pin "TP") (pinfunction "TP_TP") (pintype "input"))
      (node (ref "U5") (pin "4") (pinfunction "GND_4") (pintype "bidirectional"))
    )
    (net (code "9") (name "-9V_IO") (class "Default")
      (node (ref "PJ4") (pin "9") (pinfunction "9_9") (pintype "passive"))
      (node (ref "Q5") (pin "3") (pinfunction "D_3") (pintype "bidirectional"))
    )
    (net (code "10") (name "-22V") (class "Default")
      (node (ref "C19") (pin "2") (pinfunction "2_2") (pintype "passive"))
      (node (ref "C20") (pin "-") (pinfunction "-_-") (pintype "passive"))
      (node (ref "D10") (pin "A") (pinfunction "A_A") (pintype "passive"))
      (node (ref "D14") (pin "A") (pinfunction "A_A") (pintype "passive"))
      (node (ref "Q8") (pin "2") (pinfunction "S_2") (pintype "bidirectional"))
      (node (ref "R21") (pin "2") (pinfunction "2_2") (pintype "passive"))
      (node (ref "R37") (pin "1") (pinfunction "1_1") (pintype "passive"))
      (node (ref "R60") (pin "1") (pinfunction "1_1") (pintype "passive"))
      (node (ref "R68") (pin "2") (pinfunction "2_2") (pintype "passive"))
      (node (ref "TP4") (pin "TP") (pinfunction "TP_TP") (pintype "input"))
      (node (ref "U8") (pin "4") (pinfunction "GND_4") (pintype "bidirectional"))
    )
    (net (code "11") (name "-22V_LCD") (class "Default")
      (node (ref "PJ4") (pin "12") (pinfunction "12_12") (pintype "passive"))
      (node (ref "Q8") (pin "3") (pinfunction "D_3") (pintype "bidirectional"))
    )
    (net (code "12") (name "AIN_+5V") (class "Default")
      (node (ref "R49") (pin "2") (pinfunction "2_2") (pintype "passive"))
      (node (ref "R53") (pin "2") (pinfunction "2_2") (pintype "passive"))
      (node (ref "U13") (pin "13") (pinfunction "PB3/AIN3[TIM1_ETR]_13") (pintype "bidirectional"))
    )
    (net (code "13") (name "AIN_+12V") (class "Default")
      (node (ref "R65") (pin "2") (pinfunction "2_2") (pintype "passive"))
      (node (ref "R71") (pin "2") (pinfunction "2_2") (pintype "passive"))
      (node (ref "U15") (pin "2") (pinfunction "X6_2") (pintype "bidirectional"))
    )
    (net (code "14") (name "AIN_-9V") (class "Default")
      (node (ref "R47") (pin "2") (pinfunction "2_2") (pintype "passive"))
      (node (ref "U15") (pin "5") (pinfunction "X5_5") (pintype "bidirectional"))
      (node (ref "U17") (pin "7") (pinfunction "OUT_7") (pintype "output"))
    )
    (net (code "15") (name "AIN_-22V") (class "Default")
      (node (ref "R55") (pin "2") (pinfunction "2_2") (pintype "passive"))
      (node (ref "U15") (pin "4") (pinfunction "X7_4") (pintype "bidirectional"))
      (node (ref "U17") (pin "1") (pinfunction "OUT_1") (pintype "output"))
    )
    (net (code "16") (name "AIN_IBAT") (class "Default")
      (node (ref "R67") (pin "2") (pinfunction "2_2") (pintype "passive"))
      (node (ref "TP6") (pin "TP") (pinfunction "TP_TP") (pintype "input"))
      (node (ref "U13") (pin "15") (pinfunction "PB1/AIN1[TIM1_CH2N]_15") (pintype "bidirectional"))
      (node (ref "U4") (pin "14") (pinfunction "OUT_14") (pintype "output"))
    )
    (net (code "17") (name "AIN_IBUS") (class "Default")
      (node (ref "R46") (pin "2") (pinfunction "2_2") (pintype "passive"))
      (node (ref "TP7") (pin "TP") (pinfunction "TP_TP") (pintype "input"))
      (node (ref "U15") (pin "1") (pinfunction "X4_1") (pintype "bidirectional"))
      (node (ref "U16") (pin "1") (pinfunction "OUT_1") (pintype "output"))
    )
    (net (code "18") (name "AIN_MULTI") (class "Default")
      (node (ref "TP20") (pin "TP") (pinfunction "TP_TP") (pintype "input"))
      (node (ref "U13") (pin "16") (pinfunction "PB0/AIN0[TIM1_CH1N]_16") (pintype "bidirectional"))
      (node (ref "U15") (pin "3") (pinfunction "X_3") (pintype "bidirectional"))
    )
    (net (code "19") (name "AIN_VBAT") (class "Default")
      (node (ref "R73") (pin "2") (pinfunction "2_2") (pintype "passive"))
      (node (ref "R75") (pin "2") (pinfunction "2_2") (pintype "passive"))
      (node (ref "TP5") (pin "TP") (pinfunction "TP_TP") (pintype "input"))
      (node (ref "U13") (pin "14") (pinfunction "PB2/AIN2[TIM1_CH3N]_14") (pintype "bidirectional"))
    )
    (net (code "20") (name "AIN_VIN") (class "Default")
      (node (ref "R74") (pin "2") (pinfunction "2_2") (pintype "passive"))
      (node (ref "R76") (pin "2") (pinfunction "2_2") (pintype "passive"))
      (node (ref "TP8") (pin "TP") (pinfunction "TP_TP") (pintype "input"))
      (node (ref "U15") (pin "13") (pinfunction "X0_13") (pintype "bidirectional"))
    )
    (net (code "21") (name "CHG_B_CTRL") (class "Default")
      (node (ref "Q15") (pin "1") (pinfunction "G_1") (pintype "bidirectional"))
      (node (ref "U13") (pin "22") (pinfunction "PC5/SPI_SCK_22") (pintype "bidirectional"))
    )
    (net (code "22") (name "CHG_B_STATE") (class "Default")
      (node (ref "D17") (pin "C") (pinfunction "C_C") (pintype "passive"))
      (node (ref "R81") (pin "1") (pinfunction "1_1") (pintype "passive"))
      (node (ref "U15") (pin "15") (pinfunction "X2_15") (pintype "bidirectional"))
      (node (ref "U9") (pin "7") (pinfunction "CHRG_7") (pintype "bidirectional"))
    )
    (net (code "23") (name "CHG_B_SW") (class "Default")
      (node (ref "Q15") (pin "3") (pinfunction "D_3") (pintype "bidirectional"))
      (node (ref "R31") (pin "1") (pinfunction "1_1") (pintype "passive"))
      (node (ref "R32") (pin "1") (pinfunction "1_1") (pintype "passive"))
      (node (ref "U9") (pin "8") (pinfunction "CE_8") (pintype "bidirectional"))
    )
    (net (code "24") (name "CHG_FB") (class "Default")
      (node (ref "D5") (pin "C") (pinfunction "C_C") (pintype "passive"))
      (node (ref "R16") (pin "1") (pinfunction "1_1") (pintype "passive"))
      (node (ref "R20") (pin "2") (pinfunction "2_2") (pintype "passive"))
      (node (ref "U7") (pin "4") (pinfunction "FB_4") (pintype "input"))
    )
    (net (code "25") (name "CHG_STATE") (class "Default")
      (node (ref "R70") (pin "2") (pinfunction "2_2") (pintype "passive"))
      (node (ref "U15") (pin "14") (pinfunction "X1_14") (pintype "bidirectional"))
      (node (ref "U4") (pin "7") (pinfunction "OUT_7") (pintype "output"))
    )
    (net (code "26") (name "GND") (class "Default")
      (node (ref "C1") (pin "-") (pinfunction "-_-") (pintype "passive"))
      (node (ref "C11") (pin "+") (pinfunction "+_+") (pintype "passive"))
      (node (ref "C12") (pin "2") (pinfunction "2_2") (pintype "passive"))
      (node (ref "C13") (pin "2") (pinfunction "2_2") (pintype "passive"))
      (node (ref "C14") (pin "-") (pinfunction "-_-") (pintype "passive"))
      (node (ref "C15") (pin "-") (pinfunction "-_-") (pintype "passive"))
      (node (ref "C16") (pin "-") (pinfunction "-_-") (pintype "passive"))
      (node (ref "C17") (pin "2") (pinfunction "2_2") (pintype "passive"))
      (node (ref "C18") (pin "2") (pinfunction "2_2") (pintype "passive"))
      (node (ref "C2") (pin "2") (pinfunction "2_2") (pintype "passive"))
      (node (ref "C20") (pin "+") (pinfunction "+_+") (pintype "passive"))
      (node (ref "C21") (pin "2") (pinfunction "2_2") (pintype "passive"))
      (node (ref "C22") (pin "2") (pinfunction "2_2") (pintype "passive"))
      (node (ref "C23") (pin "2") (pinfunction "2_2") (pintype "passive"))
      (node (ref "C24") (pin "2") (pinfunction "2_2") (pintype "passive"))
      (node (ref "C25") (pin "-") (pinfunction "-_-") (pintype "passive"))
      (node (ref "C26") (pin "2") (pinfunction "2_2") (pintype "passive"))
      (node (ref "C27") (pin "2") (pinfunction "2_2") (pintype "passive"))
      (node (ref "C28") (pin "2") (pinfunction "2_2") (pintype "passive"))
      (node (ref "C29") (pin "2") (pinfunction "2_2") (pintype "passive"))
      (node (ref "C3") (pin "-") (pinfunction "-_-") (pintype "passive"))
      (node (ref "C4") (pin "2") (pinfunction "2_2") (pintype "passive"))
      (node (ref "C5") (pin "2") (pinfunction "2_2") (pintype "passive"))
      (node (ref "C6") (pin "-") (pinfunction "-_-") (pintype "passive"))
      (node (ref "C8") (pin "2") (pinfunction "2_2") (pintype "passive"))
      (node (ref "C9") (pin "-") (pinfunction "-_-") (pintype "passive"))
      (node (ref "D1") (pin "A") (pinfunction "A_A") (pintype "passive"))
      (node (ref "D16") (pin "C") (pinfunction "C_C") (pintype "passive"))
      (node (ref "D19") (pin "C") (pinfunction "C_C") (pintype "passive"))
      (node (ref "D21") (pin "C") (pinfunction "C_C") (pintype "passive"))
      (node (ref "D22") (pin "A") (pinfunction "A_A") (pintype "passive"))
      (node (ref "D23") (pin "A") (pinfunction "A_A") (pintype "passive"))
      (node (ref "D8") (pin "A") (pinfunction "A_A") (pintype "passive"))
      (node (ref "J1") (pin "3") (pinfunction "3_3") (pintype "passive"))
      (node (ref "J2") (pin "1") (pinfunction "1_1") (pintype "passive"))
      (node (ref "L3") (pin "2") (pinfunction "2_2") (pintype "passive"))
      (node (ref "L6") (pin "2") (pinfunction "2_2") (pintype "passive"))
      (node (ref "PJ1") (pin "GND") (pinfunction "GND_GND") (pintype "bidirectional"))
      (node (ref "PJ1") (pin "GNDBREAK") (pinfunction "GNDBREAK_GNDBREAK") (pintype "bidirectional"))
      (node (ref "PJ3") (pin "2") (pinfunction "2_2") (pintype "passive"))
      (node (ref "PJ4") (pin "10") (pinfunction "10_10") (pintype "passive"))
      (node (ref "PJ4") (pin "3") (pinfunction "3_3") (pintype "passive"))
      (node (ref "PJ4") (pin "7") (pinfunction "7_7") (pintype "passive"))
      (node (ref "PJ5") (pin "4") (pinfunction "4_4") (pintype "passive"))
      (node (ref "PJ6") (pin "2") (pinfunction "2_2") (pintype "passive"))
      (node (ref "Q11") (pin "2") (pinfunction "E_2") (pintype "passive"))
      (node (ref "Q13") (pin "2") (pinfunction "E_2") (pintype "passive"))
      (node (ref "Q14") (pin "2") (pinfunction "E_2") (pintype "passive"))
      (node (ref "Q3") (pin "2") (pinfunction "E_2") (pintype "passive"))
      (node (ref "R12") (pin "1") (pinfunction "1_1") (pintype "passive"))
      (node (ref "R13") (pin "1") (pinfunction "1_1") (pintype "passive"))
      (node (ref "R18") (pin "1") (pinfunction "1_1") (pintype "passive"))
      (node (ref "R19") (pin "1") (pinfunction "1_1") (pintype "passive"))
      (node (ref "R2") (pin "1") (pinfunction "1_1") (pintype "passive"))
      (node (ref "R20") (pin "1") (pinfunction "1_1") (pintype "passive"))
      (node (ref "R22") (pin "1") (pinfunction "1_1") (pintype "passive"))
      (node (ref "R26") (pin "1") (pinfunction "1_1") (pintype "passive"))
      (node (ref "R27") (pin "1") (pinfunction "1_1") (pintype "passive"))
      (node (ref "R3") (pin "1") (pinfunction "1_1") (pintype "passive"))
      (node (ref "R30") (pin "1") (pinfunction "1_1") (pintype "passive"))
      (node (ref "R34") (pin "1") (pinfunction "1_1") (pintype "passive"))
      (node (ref "R38") (pin "1") (pinfunction "1_1") (pintype "passive"))
      (node (ref "R42") (pin "2") (pinfunction "2_2") (pintype "passive"))
      (node (ref "R43") (pin "1") (pinfunction "1_1") (pintype "passive"))
      (node (ref "R48") (pin "1") (pinfunction "1_1") (pintype "passive"))
      (node (ref "R5") (pin "1") (pinfunction "1_1") (pintype "passive"))
      (node (ref "R53") (pin "1") (pinfunction "1_1") (pintype "passive"))
      (node (ref "R54") (pin "1") (pinfunction "1_1") (pintype "passive"))
      (node (ref "R56") (pin "1") (pinfunction "1_1") (pintype "passive"))
      (node (ref "R63") (pin "1") (pinfunction "1_1") (pintype "passive"))
      (node (ref "R71") (pin "1") (pinfunction "1_1") (pintype "passive"))
      (node (ref "R72") (pin "1") (pinfunction "1_1") (pintype "passive"))
      (node (ref "R75") (pin "1") (pinfunction "1_1") (pintype "passive"))
      (node (ref "R76") (pin "1") (pinfunction "1_1") (pintype "passive"))
      (node (ref "R82") (pin "1") (pinfunction "1_1") (pintype "passive"))
      (node (ref "S1") (pin "1") (pinfunction "O_1") (pintype "passive"))
      (node (ref "S1") (pin "S1") (pinfunction "SH_S1") (pintype "passive"))
      (node (ref "S1") (pin "S2") (pinfunction "SH_S2") (pintype "passive"))
      (node (ref "S2") (pin "A2") (pinfunction "1_A2") (pintype "passive"))
      (node (ref "S3") (pin "3") (pinfunction "S_3") (pintype "passive"))
      (node (ref "S3") (pin "S1") (pinfunction "SH_S1") (pintype "passive"))
      (node (ref "S3") (pin "S2") (pinfunction "SH_S2") (pintype "passive"))
      (node (ref "SJ1") (pin "2") (pinfunction "2_2") (pintype "passive"))
      (node (ref "U1") (pin "3") (pinfunction "GND_3") (pintype "power_in"))
      (node (ref "U1") (pin "TAB") (pinfunction "GND_TAB") (pintype "power_in"))
      (node (ref "U10") (pin "5") (pinfunction "I_5") (pintype "input"))
      (node (ref "U10") (pin "7") (pinfunction "VSS_7") (pintype "power_in"))
      (node (ref "U11") (pin "10") (pinfunction "COL_10") (pintype "passive"))
      (node (ref "U11") (pin "12") (pinfunction "COL_12") (pintype "passive"))
      (node (ref "U11") (pin "13") (pinfunction "EMIT_13") (pintype "passive"))
      (node (ref "U11") (pin "15") (pinfunction "EMIT_15") (pintype "passive"))
      (node (ref "U12") (pin "7") (pinfunction "GND_7") (pintype "power_in"))
      (node (ref "U13") (pin "4") (pinfunction "VSS_4") (pintype "power_in"))
      (node (ref "U14") (pin "7") (pinfunction "GND_7") (pintype "power_in"))
      (node (ref "U15") (pin "6") (pinfunction "INH_6") (pintype "input"))
      (node (ref "U15") (pin "7") (pinfunction "VEE_7") (pintype "power_in"))
      (node (ref "U15") (pin "8") (pinfunction "GND_8") (pintype "power_in"))
      (node (ref "U16") (pin "4") (pinfunction "V-_4") (pintype "power_in"))
      (node (ref "U16") (pin "5") (pinfunction "+IN_5") (pintype "input"))
      (node (ref "U17") (pin "3") (pinfunction "+IN_3") (pintype "input"))
      (node (ref "U17") (pin "4") (pinfunction "V-_4") (pintype "power_in"))
      (node (ref "U17") (pin "5") (pinfunction "+IN_5") (pintype "input"))
      (node (ref "U18") (pin "1") (pinfunction "I0_1") (pintype "input"))
      (node (ref "U18") (pin "12") (pinfunction "I0_12") (pintype "input"))
      (node (ref "U18") (pin "13") (pinfunction "I1_13") (pintype "input"))
      (node (ref "U18") (pin "2") (pinfunction "I1_2") (pintype "input"))
      (node (ref "U18") (pin "4") (pinfunction "I0_4") (pintype "input"))
      (node (ref "U18") (pin "5") (pinfunction "I1_5") (pintype "input"))
      (node (ref "U18") (pin "7") (pinfunction "GND_7") (pintype "power_in"))
      (node (ref "U2") (pin "2") (pinfunction "GND_2") (pintype "bidirectional"))
      (node (ref "U3") (pin "2") (pinfunction "GND_2") (pintype "power_in"))
      (node (ref "U3") (pin "3") (pinfunction "GND_3") (pintype "power_in"))
      (node (ref "U3") (pin "6") (pinfunction "GND_6") (pintype "power_in"))
      (node (ref "U3") (pin "7") (pinfunction "GND_7") (pintype "power_in"))
      (node (ref "U4") (pin "11") (pinfunction "V-_11") (pintype "power_in"))
      (node (ref "U6") (pin "2") (pinfunction "GND_2") (pintype "bidirectional"))
      (node (ref "U7") (pin "3") (pinfunction "GND_3") (pintype "power_in"))
      (node (ref "U7") (pin "TAB") (pinfunction "GND_TAB") (pintype "power_in"))
      (node (ref "U9") (pin "3") (pinfunction "GND_3") (pintype "bidirectional"))
      (node (ref "U9") (pin "PAD") (pinfunction "GND_PAD") (pintype "bidirectional"))
      (node (ref "VR2") (pin "1") (pinfunction "A_1") (pintype "passive"))
    )
    (net (code "27") (name "HDD5_CTRL") (class "Default")
      (node (ref "U12") (pin "9") (pinfunction "I0_9") (pintype "input"))
      (node (ref "U13") (pin "9") (pinfunction "PB7_9") (pintype "bidirectional"))
    )
    (net (code "28") (name "HDD5_EN") (class "Default")
      (node (ref "TP16") (pin "TP") (pinfunction "TP_TP") (pintype "input"))
      (node (ref "U10") (pin "3") (pinfunction "I_3") (pintype "input"))
      (node (ref "U12") (pin "1") (pinfunction "I0_1") (pintype "input"))
      (node (ref "U12") (pin "8") (pinfunction "O_8") (pintype "output"))
    )
    (net (code "29") (name "HDD12_CTRL") (class "Default")
      (node (ref "U12") (pin "2") (pinfunction "I1_2") (pintype "input"))
      (node (ref "U13") (pin "3") (pinfunction "PA2/OSCOUT_3") (pintype "bidirectional"))
    )
    (net (code "30") (name "HDD12_EN") (class "Default")
      (node (ref "TP17") (pin "TP") (pinfunction "TP_TP") (pintype "input"))
      (node (ref "U11") (pin "1") (pinfunction "A_1") (pintype "passive"))
      (node (ref "U12") (pin "3") (pinfunction "O_3") (pintype "output"))
    )
    (net (code "31") (name "LBAT") (class "Default")
      (node (ref "PJ4") (pin "11") (pinfunction "11_11") (pintype "passive"))
      (node (ref "U13") (pin "24") (pinfunction "PC7/SPI_MISO_24") (pintype "bidirectional"))
    )
    (net (code "32") (name "LED_G") (class "Default")
      (node (ref "D15") (pin "AX") (pinfunction "AG_AX") (pintype "passive"))
      (node (ref "U13") (pin "27") (pinfunction "PD2[TIM2_CH3]_27") (pintype "bidirectional"))
    )
    (net (code "33") (name "LED_R") (class "Default")
      (node (ref "D15") (pin "AR") (pinfunction "AR_AR") (pintype "passive"))
      (node (ref "U13") (pin "28") (pinfunction "PD3/TIM2_CH2[ADC_ETR]_28") (pintype "bidirectional"))
    )
    (net (code "34") (name "MAIN_CTRL") (class "Default")
      (node (ref "TP24") (pin "TP") (pinfunction "TP_TP") (pintype "input"))
      (node (ref "U13") (pin "7") (pinfunction "PA3/TIM2_CH3[SPI_NSS]_7") (pintype "bidirectional"))
      (node (ref "U14") (pin "10") (pinfunction "I1_10") (pintype "input"))
    )
    (net (code "35") (name "MAIN_EN") (class "Default")
      (node (ref "TP15") (pin "TP") (pinfunction "TP_TP") (pintype "input"))
      (node (ref "U10") (pin "1") (pinfunction "I_1") (pintype "input"))
      (node (ref "U11") (pin "3") (pinfunction "A_3") (pintype "passive"))
      (node (ref "U11") (pin "5") (pinfunction "A_5") (pintype "passive"))
      (node (ref "U11") (pin "7") (pinfunction "A_7") (pintype "passive"))
      (node (ref "U12") (pin "10") (pinfunction "I1_10") (pintype "input"))
      (node (ref "U14") (pin "6") (pinfunction "O_6") (pintype "output"))
      (node (ref "U18") (pin "10") (pinfunction "I1_10") (pintype "input"))
    )
    (net (code "36") (name "MEM_BACKUP") (class "Default")
      (node (ref "R78") (pin "1") (pinfunction "1_1") (pintype "passive"))
      (node (ref "TP19") (pin "TP") (pinfunction "TP_TP") (pintype "input"))
      (node (ref "U12") (pin "11") (pinfunction "O_11") (pintype "output"))
    )
    (net (code "37") (name "MEM_CTRL") (class "Default")
      (node (ref "TP23") (pin "TP") (pinfunction "TP_TP") (pintype "input"))
      (node (ref "U12") (pin "12") (pinfunction "I0_12") (pintype "input"))
      (node (ref "U13") (pin "10") (pinfunction "PB6_10") (pintype "bidirectional"))
      (node (ref "U18") (pin "9") (pinfunction "I0_9") (pintype "input"))
    )
    (net (code "38") (name "MEM_EN") (class "Default")
      (node (ref "U12") (pin "4") (pinfunction "I0_4") (pintype "input"))
      (node (ref "U18") (pin "8") (pinfunction "O_8") (pintype "output"))
    )
    (net (code "39") (name "MEM_MAIN") (class "Default")
      (node (ref "R80") (pin "1") (pinfunction "1_1") (pintype "passive"))
      (node (ref "TP18") (pin "TP") (pinfunction "TP_TP") (pintype "input"))
      (node (ref "U12") (pin "6") (pinfunction "O_6") (pintype "output"))
    )
    (net (code "40") (name "MUL_A") (class "Default")
      (node (ref "U13") (pin "18") (pinfunction "PC1/TIM1_CH1/UART1_CK_18") (pintype "bidirectional"))
      (node (ref "U15") (pin "11") (pinfunction "A_11") (pintype "input"))
    )
    (net (code "41") (name "MUL_B") (class "Default")
      (node (ref "U13") (pin "20") (pinfunction "PC3/TIM1_CH3_20") (pintype "bidirectional"))
      (node (ref "U15") (pin "10") (pinfunction "B_10") (pintype "input"))
    )
    (net (code "42") (name "MUL_C") (class "Default")
      (node (ref "U13") (pin "19") (pinfunction "PC2/TIM1_CH2_19") (pintype "bidirectional"))
      (node (ref "U15") (pin "9") (pinfunction "C_9") (pintype "input"))
    )
    (net (code "43") (name "NRST") (class "Default")
      (node (ref "J1") (pin "4") (pinfunction "4_4") (pintype "passive"))
      (node (ref "U13") (pin "1") (pinfunction "NRST_1") (pintype "bidirectional"))
    )
    (net (code "44") (name "Net-(D15-PadC)") (class "Default")
      (node (ref "D15") (pin "C") (pinfunction "C_C") (pintype "passive"))
      (node (ref "R43") (pin "2") (pinfunction "2_2") (pintype "passive"))
    )
    (net (code "45") (name "Net-(D16-PadA)") (class "Default")
      (node (ref "D16") (pin "A") (pinfunction "A_A") (pintype "passive"))
      (node (ref "R57") (pin "1") (pinfunction "1_1") (pintype "passive"))
    )
    (net (code "46") (name "Net-(D17-PadA)") (class "Default")
      (node (ref "D17") (pin "A") (pinfunction "A_A") (pintype "passive"))
      (node (ref "JP2") (pin "2") (pinfunction "2_2") (pintype "passive"))
    )
    (net (code "47") (name "Net-(D19-PadA)") (class "Default")
      (node (ref "D19") (pin "A") (pinfunction "A_A") (pintype "passive"))
      (node (ref "R62") (pin "1") (pinfunction "1_1") (pintype "passive"))
    )
    (net (code "48") (name "Net-(D21-PadA)") (class "Default")
      (node (ref "D21") (pin "A") (pinfunction "A_A") (pintype "passive"))
      (node (ref "JP1") (pin "2") (pinfunction "2_2") (pintype "passive"))
    )
    (net (code "49") (name "Net-(D22-PadC)") (class "Default")
      (node (ref "D22") (pin "C") (pinfunction "C_C") (pintype "passive"))
      (node (ref "R64") (pin "1") (pinfunction "1_1") (pintype "passive"))
    )
    (net (code "50") (name "Net-(D23-PadC)") (class "Default")
      (node (ref "D23") (pin "C") (pinfunction "C_C") (pintype "passive"))
      (node (ref "R68") (pin "1") (pinfunction "1_1") (pintype "passive"))
    )
    (net (code "51") (name "Net-(F1-Pad2)") (class "Default")
      (node (ref "F1") (pin "2") (pinfunction "2_2") (pintype "passive"))
      (node (ref "PJ2") (pin "1") (pinfunction "1_1") (pintype "passive"))
    )
    (net (code "52") (name "Net-(JP1-Pad1)") (class "Default")
      (node (ref "JP1") (pin "1") (pinfunction "1_1") (pintype "passive"))
      (node (ref "R70") (pin "1") (pinfunction "1_1") (pintype "passive"))
    )
    (net (code "53") (name "Net-(JP2-Pad1)") (class "Default")
      (node (ref "JP2") (pin "1") (pinfunction "1_1") (pintype "passive"))
      (node (ref "R69") (pin "1") (pinfunction "1_1") (pintype "passive"))
    )
    (net (code "54") (name "Net-(Q2-D)") (class "Default")
      (node (ref "C4") (pin "1") (pinfunction "1_1") (pintype "passive"))
      (node (ref "C9") (pin "+") (pinfunction "+_+") (pintype "passive"))
      (node (ref "L2") (pin "1") (pinfunction "1_1") (pintype "passive"))
      (node (ref "Q2") (pin "3") (pinfunction "D_3") (pintype "bidirectional"))
      (node (ref "R10") (pin "1") (pinfunction "1_1") (pintype "passive"))
      (node (ref "R17") (pin "1") (pinfunction "1_1") (pintype "passive"))
      (node (ref "U2") (pin "4") (pinfunction "EN_4") (pintype "bidirectional"))
      (node (ref "U2") (pin "5") (pinfunction "VIN_5") (pintype "bidirectional"))
      (node (ref "U5") (pin "6") (pinfunction "VCC_6") (pintype "bidirectional"))
      (node (ref "U8") (pin "6") (pinfunction "VCC_6") (pintype "bidirectional"))
    )
    (net (code "55") (name "Net-(Q2-G)") (class "Default")
      (node (ref "Q2") (pin "1") (pinfunction "G_1") (pintype "bidirectional"))
      (node (ref "Q3") (pin "3") (pinfunction "C_3") (pintype "passive"))
      (node (ref "R6") (pin "1") (pinfunction "1_1") (pintype "passive"))
    )
    (net (code "56") (name "Net-(Q3-B)") (class "Default")
      (node (ref "Q3") (pin "1") (pinfunction "B_1") (pintype "passive"))
      (node (ref "R7") (pin "2") (pinfunction "2_2") (pintype "passive"))
    )
    (net (code "57") (name "Net-(Q4-D)") (class "Default")
      (node (ref "D12") (pin "A") (pinfunction "A_A") (pintype "passive"))
      (node (ref "Q4") (pin "3") (pinfunction "D_3") (pintype "bidirectional"))
    )
    (net (code "58") (name "Net-(Q5-G)") (class "Default")
      (node (ref "Q5") (pin "1") (pinfunction "G_1") (pintype "bidirectional"))
      (node (ref "R29") (pin "2") (pinfunction "2_2") (pintype "passive"))
      (node (ref "U11") (pin "11") (pinfunction "EMIT_11") (pintype "passive"))
    )
    (net (code "59") (name "Net-(Q6-G)") (class "Default")
      (node (ref "Q6") (pin "1") (pinfunction "G_1") (pintype "bidirectional"))
      (node (ref "U10") (pin "2") (pinfunction "O_2") (pintype "output"))
    )
    (net (code "60") (name "Net-(Q7-G)") (class "Default")
      (node (ref "D11") (pin "A") (pinfunction "A_A") (pintype "passive"))
      (node (ref "Q7") (pin "1") (pinfunction "G_1") (pintype "bidirectional"))
      (node (ref "R25") (pin "1") (pinfunction "1_1") (pintype "passive"))
      (node (ref "R28") (pin "2") (pinfunction "2_2") (pintype "passive"))
    )
    (net (code "61") (name "Net-(Q8-G)") (class "Default")
      (node (ref "D14") (pin "C") (pinfunction "C_C") (pintype "passive"))
      (node (ref "Q8") (pin "1") (pinfunction "G_1") (pintype "bidirectional"))
      (node (ref "R35") (pin "2") (pinfunction "2_2") (pintype "passive"))
      (node (ref "R37") (pin "2") (pinfunction "2_2") (pintype "passive"))
    )
    (net (code "62") (name "Net-(Q9-G)") (class "Default")
      (node (ref "Q9") (pin "1") (pinfunction "G_1") (pintype "bidirectional"))
      (node (ref "U10") (pin "4") (pinfunction "O_4") (pintype "output"))
    )
    (net (code "63") (name "Net-(Q10-G)") (class "Default")
      (node (ref "D13") (pin "A") (pinfunction "A_A") (pintype "passive"))
      (node (ref "Q10") (pin "1") (pinfunction "G_1") (pintype "bidirectional"))
      (node (ref "R33") (pin "1") (pinfunction "1_1") (pintype "passive"))
      (node (ref "R36") (pin "2") (pinfunction "2_2") (pintype "passive"))
    )
    (net (code "64") (name "Net-(Q11-B)") (class "Default")
      (node (ref "Q11") (pin "1") (pinfunction "B_1") (pintype "passive"))
      (node (ref "R39") (pin "1") (pinfunction "1_1") (pintype "passive"))
    )
    (net (code "65") (name "Net-(Q12-G)") (class "Default")
      (node (ref "Q12") (pin "1") (pinfunction "G_1") (pintype "bidirectional"))
      (node (ref "Q13") (pin "3") (pinfunction "C_3") (pintype "passive"))
      (node (ref "R77") (pin "1") (pinfunction "1_1") (pintype "passive"))
    )
    (net (code "66") (name "Net-(Q13-B)") (class "Default")
      (node (ref "Q13") (pin "1") (pinfunction "B_1") (pintype "passive"))
      (node (ref "R78") (pin "2") (pinfunction "2_2") (pintype "passive"))
    )
    (net (code "67") (name "Net-(Q14-B)") (class "Default")
      (node (ref "Q14") (pin "1") (pinfunction "B_1") (pintype "passive"))
      (node (ref "R80") (pin "2") (pinfunction "2_2") (pintype "passive"))
    )
    (net (code "68") (name "Net-(Q14-C)") (class "Default")
      (node (ref "Q14") (pin "3") (pinfunction "C_3") (pintype "passive"))
      (node (ref "Q4") (pin "1") (pinfunction "G_1") (pintype "bidirectional"))
      (node (ref "R79") (pin "1") (pinfunction "1_1") (pintype "passive"))
    )
    (net (code "69") (name "Net-(R22-Pad2)") (class "Default")
      (node (ref "R22") (pin "2") (pinfunction "2_2") (pintype "passive"))
      (node (ref "R23") (pin "2") (pinfunction "2_2") (pintype "passive"))
    )
    (net (code "70") (name "Net-(R23-Pad1)") (class "Default")
      (node (ref "R23") (pin "1") (pinfunction "1_1") (pintype "passive"))
      (node (ref "R24") (pin "1") (pinfunction "1_1") (pintype "passive"))
    )
    (net (code "71") (name "Net-(R48-Pad2)") (class "Default")
      (node (ref "R48") (pin "2") (pinfunction "2_2") (pintype "passive"))
      (node (ref "R50") (pin "1") (pinfunction "1_1") (pintype "passive"))
      (node (ref "R51") (pin "2") (pinfunction "2_2") (pintype "passive"))
    )
    (net (code "72") (name "Net-(R56-Pad2)") (class "Default")
      (node (ref "R56") (pin "2") (pinfunction "2_2") (pintype "passive"))
      (node (ref "R58") (pin "1") (pinfunction "1_1") (pintype "passive"))
      (node (ref "R60") (pin "2") (pinfunction "2_2") (pintype "passive"))
    )
    (net (code "73") (name "Net-(U1-FB)") (class "Default")
      (node (ref "R1") (pin "1") (pinfunction "1_1") (pintype "passive"))
      (node (ref "R3") (pin "2") (pinfunction "2_2") (pintype "passive"))
      (node (ref "U1") (pin "4") (pinfunction "FB_4") (pintype "input"))
    )
    (net (code "74") (name "Net-(U1-OUT)") (class "Default")
      (node (ref "D1") (pin "C") (pinfunction "C_C") (pintype "passive"))
      (node (ref "L1") (pin "1") (pinfunction "1_1") (pintype "passive"))
      (node (ref "U1") (pin "2") (pinfunction "OUT_2") (pintype "output"))
    )
    (net (code "75") (name "Net-(U2-FB)") (class "Default")
      (node (ref "R4") (pin "1") (pinfunction "1_1") (pintype "passive"))
      (node (ref "R5") (pin "2") (pinfunction "2_2") (pintype "passive"))
      (node (ref "U2") (pin "3") (pinfunction "FB_3") (pintype "bidirectional"))
    )
    (net (code "76") (name "Net-(U2-SW)") (class "Default")
      (node (ref "D3") (pin "A") (pinfunction "A_A") (pintype "passive"))
      (node (ref "L2") (pin "2") (pinfunction "2_2") (pintype "passive"))
      (node (ref "U2") (pin "1") (pinfunction "SW_1") (pintype "bidirectional"))
    )
    (net (code "77") (name "Net-(U4A--IN)") (class "Default")
      (node (ref "C7") (pin "1") (pinfunction "1_1") (pintype "passive"))
      (node (ref "R11") (pin "2") (pinfunction "2_2") (pintype "passive"))
      (node (ref "U4") (pin "2") (pinfunction "-IN_2") (pintype "input"))
      (node (ref "VR1") (pin "2") (pinfunction "S_2") (pintype "passive"))
    )
    (net (code "78") (name "Net-(U4A-OUT)") (class "Default")
      (node (ref "C7") (pin "2") (pinfunction "2_2") (pintype "passive"))
      (node (ref "D5") (pin "A") (pinfunction "A_A") (pintype "passive"))
      (node (ref "U4") (pin "1") (pinfunction "OUT_1") (pintype "output"))
    )
    (net (code "79") (name "Net-(U4B--IN)") (class "Default")
      (node (ref "U4") (pin "6") (pinfunction "-IN_6") (pintype "input"))
      (node (ref "VR2") (pin "2") (pinfunction "S_2") (pintype "passive"))
    )
    (net (code "80") (name "Net-(U4C-+IN)") (class "Default")
      (node (ref "R52") (pin "1") (pinfunction "1_1") (pintype "passive"))
      (node (ref "R54") (pin "2") (pinfunction "2_2") (pintype "passive"))
      (node (ref "U4") (pin "10") (pinfunction "+IN_10") (pintype "input"))
    )
    (net (code "81") (name "Net-(U4C--IN)") (class "Default")
      (node (ref "R59") (pin "2") (pinfunction "2_2") (pintype "passive"))
      (node (ref "U4") (pin "8") (pinfunction "OUT_8") (pintype "output"))
      (node (ref "U4") (pin "9") (pinfunction "-IN_9") (pintype "input"))
    )
    (net (code "82") (name "Net-(U4D-+IN)") (class "Default")
      (node (ref "R59") (pin "1") (pinfunction "1_1") (pintype "passive"))
      (node (ref "R61") (pin "2") (pinfunction "2_2") (pintype "passive"))
      (node (ref "U4") (pin "12") (pinfunction "+IN_12") (pintype "input"))
    )
    (net (code "83") (name "Net-(U4D--IN)") (class "Default")
      (node (ref "R63") (pin "2") (pinfunction "2_2") (pintype "passive"))
      (node (ref "R67") (pin "1") (pinfunction "1_1") (pintype "passive"))
      (node (ref "U4") (pin "13") (pinfunction "-IN_13") (pintype "input"))
    )
    (net (code "84") (name "Net-(U5-COMP)") (class "Default")
      (node (ref "R13") (pin "2") (pinfunction "2_2") (pintype "passive"))
      (node (ref "R14") (pin "1") (pinfunction "1_1") (pintype "passive"))
      (node (ref "U5") (pin "5") (pinfunction "COMP_5") (pintype "bidirectional"))
    )
    (net (code "85") (name "Net-(U5-DVR)") (class "Default")
      (node (ref "R10") (pin "2") (pinfunction "2_2") (pintype "passive"))
      (node (ref "U5") (pin "1") (pinfunction "SWC_1") (pintype "bidirectional"))
      (node (ref "U5") (pin "7") (pinfunction "SEN_7") (pintype "bidirectional"))
      (node (ref "U5") (pin "8") (pinfunction "DVR_8") (pintype "bidirectional"))
    )
    (net (code "86") (name "Net-(U5-SWE)") (class "Default")
      (node (ref "D7") (pin "C") (pinfunction "C_C") (pintype "passive"))
      (node (ref "L3") (pin "1") (pinfunction "1_1") (pintype "passive"))
      (node (ref "U5") (pin "2") (pinfunction "SWE_2") (pintype "bidirectional"))
    )
    (net (code "87") (name "Net-(U5-TC)") (class "Default")
      (node (ref "C10") (pin "1") (pinfunction "1_1") (pintype "passive"))
      (node (ref "U5") (pin "3") (pinfunction "TC_3") (pintype "bidirectional"))
    )
    (net (code "88") (name "Net-(U6-FB)") (class "Default")
      (node (ref "R15") (pin "1") (pinfunction "1_1") (pintype "passive"))
      (node (ref "R18") (pin "2") (pinfunction "2_2") (pintype "passive"))
      (node (ref "U6") (pin "3") (pinfunction "FB_3") (pintype "bidirectional"))
    )
    (net (code "89") (name "Net-(U6-SW)") (class "Default")
      (node (ref "D9") (pin "A") (pinfunction "A_A") (pintype "passive"))
      (node (ref "L4") (pin "2") (pinfunction "2_2") (pintype "passive"))
      (node (ref "U6") (pin "1") (pinfunction "SW_1") (pintype "bidirectional"))
    )
    (net (code "90") (name "Net-(U7-OUT)") (class "Default")
      (node (ref "D8") (pin "C") (pinfunction "C_C") (pintype "passive"))
      (node (ref "L5") (pin "1") (pinfunction "1_1") (pintype "passive"))
      (node (ref "U7") (pin "2") (pinfunction "OUT_2") (pintype "output"))
    )
    (net (code "91") (name "Net-(U8-COMP)") (class "Default")
      (node (ref "R21") (pin "1") (pinfunction "1_1") (pintype "passive"))
      (node (ref "R24") (pin "2") (pinfunction "2_2") (pintype "passive"))
      (node (ref "U8") (pin "5") (pinfunction "COMP_5") (pintype "bidirectional"))
    )
    (net (code "92") (name "Net-(U8-DVR)") (class "Default")
      (node (ref "R17") (pin "2") (pinfunction "2_2") (pintype "passive"))
      (node (ref "U8") (pin "1") (pinfunction "SWC_1") (pintype "bidirectional"))
      (node (ref "U8") (pin "7") (pinfunction "SEN_7") (pintype "bidirectional"))
      (node (ref "U8") (pin "8") (pinfunction "DVR_8") (pintype "bidirectional"))
    )
    (net (code "93") (name "Net-(U8-SWE)") (class "Default")
      (node (ref "D10") (pin "C") (pinfunction "C_C") (pintype "passive"))
      (node (ref "L6") (pin "1") (pinfunction "1_1") (pintype "passive"))
      (node (ref "U8") (pin "2") (pinfunction "SWE_2") (pintype "bidirectional"))
    )
    (net (code "94") (name "Net-(U8-TC)") (class "Default")
      (node (ref "C19") (pin "1") (pinfunction "1_1") (pintype "passive"))
      (node (ref "U8") (pin "3") (pinfunction "TC_3") (pintype "bidirectional"))
    )
    (net (code "95") (name "Net-(U9-PROG)") (class "Default")
      (node (ref "R27") (pin "2") (pinfunction "2_2") (pintype "passive"))
      (node (ref "U9") (pin "2") (pinfunction "PROG_2") (pintype "bidirectional"))
    )
    (net (code "96") (name "Net-(U9-VCC)") (class "Default")
      (node (ref "C21") (pin "1") (pinfunction "1_1") (pintype "passive"))
      (node (ref "R31") (pin "2") (pinfunction "2_2") (pintype "passive"))
      (node (ref "R32") (pin "2") (pinfunction "2_2") (pintype "passive"))
      (node (ref "U9") (pin "4") (pinfunction "VCC_4") (pintype "bidirectional"))
    )
    (net (code "97") (name "Net-(U10F-O)") (class "Default")
      (node (ref "U10") (pin "12") (pinfunction "O_12") (pintype "output"))
      (node (ref "U12") (pin "13") (pinfunction "I1_13") (pintype "input"))
    )
    (net (code "98") (name "Net-(U11A-C)") (class "Default")
      (node (ref "R38") (pin "2") (pinfunction "2_2") (pintype "passive"))
      (node (ref "U11") (pin "2") (pinfunction "C_2") (pintype "passive"))
    )
    (net (code "99") (name "Net-(U11A-COL)") (class "Default")
      (node (ref "R36") (pin "1") (pinfunction "1_1") (pintype "passive"))
      (node (ref "U11") (pin "16") (pinfunction "COL_16") (pintype "passive"))
    )
    (net (code "100") (name "Net-(U11B-C)") (class "Default")
      (node (ref "R30") (pin "2") (pinfunction "2_2") (pintype "passive"))
      (node (ref "U11") (pin "4") (pinfunction "C_4") (pintype "passive"))
    )
    (net (code "101") (name "Net-(U11B-COL)") (class "Default")
      (node (ref "R28") (pin "1") (pinfunction "1_1") (pintype "passive"))
      (node (ref "U11") (pin "14") (pinfunction "COL_14") (pintype "passive"))
    )
    (net (code "102") (name "Net-(U11C-C)") (class "Default")
      (node (ref "R26") (pin "2") (pinfunction "2_2") (pintype "passive"))
      (node (ref "U11") (pin "6") (pinfunction "C_6") (pintype "passive"))
    )
    (net (code "103") (name "Net-(U11D-C)") (class "Default")
      (node (ref "R34") (pin "2") (pinfunction "2_2") (pintype "passive"))
      (node (ref "U11") (pin "8") (pinfunction "C_8") (pintype "passive"))
    )
    (net (code "104") (name "Net-(U11D-EMIT)") (class "Default")
      (node (ref "R35") (pin "1") (pinfunction "1_1") (pintype "passive"))
      (node (ref "U11") (pin "9") (pinfunction "EMIT_9") (pintype "passive"))
    )
    (net (code "105") (name "Net-(U13-PD5{slash}UART1_TX)") (class "Default")
      (node (ref "R40") (pin "1") (pinfunction "1_1") (pintype "passive"))
      (node (ref "U13") (pin "30") (pinfunction "PD5/UART1_TX_30") (pintype "bidirectional"))
    )
    (net (code "106") (name "Net-(U13-VCAP)") (class "Default")
      (node (ref "C23") (pin "1") (pinfunction "1_1") (pintype "passive"))
      (node (ref "U13") (pin "5") (pinfunction "VCAP_5") (pintype "power_in"))
    )
    (net (code "107") (name "Net-(U14A-I0)") (class "Default")
      (node (ref "U14") (pin "1") (pinfunction "I0_1") (pintype "input"))
      (node (ref "U14") (pin "11") (pinfunction "O_11") (pintype "output"))
    )
    (net (code "108") (name "Net-(U14B-I0)") (class "Default")
      (node (ref "U14") (pin "4") (pinfunction "I0_4") (pintype "input"))
      (node (ref "U14") (pin "8") (pinfunction "O_8") (pintype "output"))
    )
    (net (code "109") (name "Net-(U16A-+IN)") (class "Default")
      (node (ref "R42") (pin "1") (pinfunction "1_1") (pintype "passive"))
      (node (ref "R44") (pin "2") (pinfunction "2_2") (pintype "passive"))
      (node (ref "U16") (pin "3") (pinfunction "+IN_3") (pintype "input"))
    )
    (net (code "110") (name "Net-(U16A--IN)") (class "Default")
      (node (ref "R45") (pin "2") (pinfunction "2_2") (pintype "passive"))
      (node (ref "R46") (pin "1") (pinfunction "1_1") (pintype "passive"))
      (node (ref "U16") (pin "2") (pinfunction "-IN_2") (pintype "input"))
    )
    (net (code "111") (name "Net-(U16B--IN)") (class "Default")
      (node (ref "U16") (pin "6") (pinfunction "-IN_6") (pintype "input"))
      (node (ref "U16") (pin "7") (pinfunction "OUT_7") (pintype "output"))
    )
    (net (code "112") (name "Net-(U17A--IN)") (class "Default")
      (node (ref "R55") (pin "1") (pinfunction "1_1") (pintype "passive"))
      (node (ref "R58") (pin "2") (pinfunction "2_2") (pintype "passive"))
      (node (ref "U17") (pin "2") (pinfunction "-IN_2") (pintype "input"))
    )
    (net (code "113") (name "Net-(U17B--IN)") (class "Default")
      (node (ref "R47") (pin "1") (pinfunction "1_1") (pintype "passive"))
      (node (ref "R50") (pin "2") (pinfunction "2_2") (pintype "passive"))
      (node (ref "U17") (pin "6") (pinfunction "-IN_6") (pintype "input"))
    )
    (net (code "114") (name "Net-(VR1-A)") (class "Default")
      (node (ref "R12") (pin "2") (pinfunction "2_2") (pintype "passive"))
      (node (ref "VR1") (pin "1") (pinfunction "A_1") (pintype "passive"))
    )
    (net (code "115") (name "Net-(VR1-E)") (class "Default")
      (node (ref "R9") (pin "1") (pinfunction "1_1") (pintype "passive"))
      (node (ref "VR1") (pin "3") (pinfunction "E_3") (pintype "passive"))
    )
    (net (code "116") (name "Net-(VR2-E)") (class "Default")
      (node (ref "R11") (pin "1") (pinfunction "1_1") (pintype "passive"))
      (node (ref "VR2") (pin "3") (pinfunction "E_3") (pintype "passive"))
    )
    (net (code "117") (name "PRI_CTRL") (class "Default")
      (node (ref "TP21") (pin "TP") (pinfunction "TP_TP") (pintype "input"))
      (node (ref "U10") (pin "11") (pinfunction "I_11") (pintype "input"))
      (node (ref "U13") (pin "21") (pinfunction "PC4/TIM1_CH4/CLK_CCO_21") (pintype "bidirectional"))
      (node (ref "U14") (pin "12") (pinfunction "I0_12") (pintype "input"))
    )
    (net (code "118") (name "PRI_OK") (class "Default")
      (node (ref "TP14") (pin "TP") (pinfunction "TP_TP") (pintype "input"))
      (node (ref "U10") (pin "13") (pinfunction "I_13") (pintype "input"))
      (node (ref "U12") (pin "5") (pinfunction "I1_5") (pintype "input"))
      (node (ref "U14") (pin "3") (pinfunction "O_3") (pintype "output"))
      (node (ref "U14") (pin "5") (pinfunction "I1_5") (pintype "input"))
    )
    (net (code "119") (name "PRI_OK_CTRL") (class "Default")
      (node (ref "TP25") (pin "TP") (pinfunction "TP_TP") (pintype "input"))
      (node (ref "U13") (pin "8") (pinfunction "PF4_8") (pintype "bidirectional"))
      (node (ref "U14") (pin "13") (pinfunction "I1_13") (pintype "input"))
    )
    (net (code "120") (name "RSTIN") (class "Default")
      (node (ref "PJ4") (pin "4") (pinfunction "4_4") (pintype "passive"))
      (node (ref "U13") (pin "25") (pinfunction "PD0/TIM1_BKIN[CLK_CCO]_25") (pintype "bidirectional"))
    )
    (net (code "121") (name "RSTOUT") (class "Default")
      (node (ref "C25") (pin "+") (pinfunction "+_+") (pintype "passive"))
      (node (ref "PJ4") (pin "5") (pinfunction "5_5") (pintype "passive"))
      (node (ref "Q11") (pin "3") (pinfunction "C_3") (pintype "passive"))
      (node (ref "S2") (pin "B2") (pinfunction "2_B2") (pintype "passive"))
    )
    (net (code "122") (name "RST_MCU") (class "Default")
      (node (ref "R39") (pin "2") (pinfunction "2_2") (pintype "passive"))
      (node (ref "U13") (pin "29") (pinfunction "PD4/BEEP/TIM2_CH1_29") (pintype "bidirectional"))
    )
    (net (code "123") (name "RX") (class "Default")
      (node (ref "J2") (pin "3") (pinfunction "3_3") (pintype "passive"))
      (node (ref "PJ4") (pin "2") (pinfunction "2_2") (pintype "passive"))
      (node (ref "R41") (pin "1") (pinfunction "1_1") (pintype "passive"))
      (node (ref "U13") (pin "31") (pinfunction "PD6/UART1_RX_31") (pintype "bidirectional"))
    )
    (net (code "124") (name "SEC_CTRL") (class "Default")
      (node (ref "R7") (pin "1") (pinfunction "1_1") (pintype "passive"))
      (node (ref "TP22") (pin "TP") (pinfunction "TP_TP") (pintype "input"))
      (node (ref "U13") (pin "23") (pinfunction "PC6/SPI_MOSI_23") (pintype "bidirectional"))
      (node (ref "U14") (pin "9") (pinfunction "I0_9") (pintype "input"))
    )
    (net (code "125") (name "SEC_VIN") (class "Default")
      (node (ref "Q2") (pin "2") (pinfunction "S_2") (pintype "bidirectional"))
      (node (ref "R6") (pin "2") (pinfunction "2_2") (pintype "passive"))
      (node (ref "SJ2") (pin "2") (pinfunction "2_2") (pintype "passive"))
    )
    (net (code "126") (name "SWIM") (class "Default")
      (node (ref "J1") (pin "2") (pinfunction "2_2") (pintype "passive"))
      (node (ref "U13") (pin "26") (pinfunction "PD1/SWIM_26") (pintype "bidirectional"))
    )
    (net (code "127") (name "TX") (class "Default")
      (node (ref "J2") (pin "2") (pinfunction "2_2") (pintype "passive"))
      (node (ref "PJ4") (pin "1") (pinfunction "1_1") (pintype "passive"))
      (node (ref "R40") (pin "2") (pinfunction "2_2") (pintype "passive"))
    )
    (net (code "128") (name "V+") (class "Default")
      (node (ref "C3") (pin "+") (pinfunction "+_+") (pintype "passive"))
      (node (ref "D2") (pin "C") (pinfunction "C_C") (pintype "passive"))
      (node (ref "Q1") (pin "3") (pinfunction "S_3") (pintype "bidirectional"))
      (node (ref "R66") (pin "1") (pinfunction "1_1") (pintype "passive"))
      (node (ref "SJ2") (pin "1") (pinfunction "1_1") (pintype "passive"))
      (node (ref "TP11") (pin "TP") (pinfunction "TP_TP") (pintype "input"))
      (node (ref "U1") (pin "1") (pinfunction "IN_1") (pintype "input"))
      (node (ref "U3") (pin "8") (pinfunction "VIN_8") (pintype "passive"))
    )
    (net (code "129") (name "V+SENSE") (class "Default")
      (node (ref "R66") (pin "2") (pinfunction "2_2") (pintype "passive"))
      (node (ref "R72") (pin "2") (pinfunction "2_2") (pintype "passive"))
      (node (ref "U13") (pin "12") (pinfunction "PB4/I2C_SCL_12") (pintype "bidirectional"))
    )
    (net (code "130") (name "VBACKUP") (class "Default")
      (node (ref "C22") (pin "1") (pinfunction "1_1") (pintype "passive"))
      (node (ref "D4") (pin "A") (pinfunction "A_A") (pintype "passive"))
      (node (ref "PJ3") (pin "1") (pinfunction "1_1") (pintype "passive"))
      (node (ref "Q12") (pin "2") (pinfunction "S_2") (pintype "bidirectional"))
      (node (ref "R77") (pin "2") (pinfunction "2_2") (pintype "passive"))
      (node (ref "R82") (pin "2") (pinfunction "2_2") (pintype "passive"))
      (node (ref "U15") (pin "12") (pinfunction "X3_12") (pintype "bidirectional"))
      (node (ref "U9") (pin "5") (pinfunction "BAT_5") (pintype "bidirectional"))
    )
    (net (code "131") (name "VBACKUP_SW") (class "Default")
      (node (ref "C12") (pin "1") (pinfunction "1_1") (pintype "passive"))
      (node (ref "L4") (pin "1") (pinfunction "1_1") (pintype "passive"))
      (node (ref "Q12") (pin "3") (pinfunction "D_3") (pintype "bidirectional"))
      (node (ref "U6") (pin "4") (pinfunction "EN_4") (pintype "bidirectional"))
      (node (ref "U6") (pin "5") (pinfunction "VIN_5") (pintype "bidirectional"))
    )
    (net (code "132") (name "VBAT+") (class "Default")
      (node (ref "C16") (pin "+") (pinfunction "+_+") (pintype "passive"))
      (node (ref "C17") (pin "1") (pinfunction "1_1") (pintype "passive"))
      (node (ref "F1") (pin "1") (pinfunction "1_1") (pintype "passive"))
      (node (ref "L5") (pin "2") (pinfunction "2_2") (pintype "passive"))
      (node (ref "Q1") (pin "2") (pinfunction "D_2") (pintype "bidirectional"))
      (node (ref "R16") (pin "2") (pinfunction "2_2") (pintype "passive"))
      (node (ref "R73") (pin "1") (pinfunction "1_1") (pintype "passive"))
    )
    (net (code "133") (name "VBAT-") (class "Default")
      (node (ref "PJ2") (pin "2") (pinfunction "2_2") (pintype "passive"))
      (node (ref "R19") (pin "2") (pinfunction "2_2") (pintype "passive"))
      (node (ref "R61") (pin "1") (pinfunction "1_1") (pintype "passive"))
      (node (ref "U4") (pin "3") (pinfunction "+IN_3") (pintype "input"))
      (node (ref "U4") (pin "5") (pinfunction "+IN_5") (pintype "input"))
    )
    (net (code "134") (name "VBTEMP") (class "Default")
      (node (ref "PJ3") (pin "3") (pinfunction "3_3") (pintype "passive"))
      (node (ref "SJ1") (pin "1") (pinfunction "1_1") (pintype "passive"))
      (node (ref "U9") (pin "1") (pinfunction "TEMP_1") (pintype "bidirectional"))
    )
    (net (code "135") (name "VBUS") (class "Default")
      (node (ref "F2") (pin "1") (pinfunction "1_1") (pintype "passive"))
      (node (ref "PJ1") (pin "PWR") (pinfunction "PWR_PWR") (pintype "bidirectional"))
    )
    (net (code "136") (name "VCCINT") (class "Default")
      (node (ref "C18") (pin "1") (pinfunction "1_1") (pintype "passive"))
      (node (ref "C26") (pin "1") (pinfunction "1_1") (pintype "passive"))
      (node (ref "C8") (pin "1") (pinfunction "1_1") (pintype "passive"))
      (node (ref "D6") (pin "A") (pinfunction "A_A") (pintype "passive"))
      (node (ref "R52") (pin "2") (pinfunction "2_2") (pintype "passive"))
      (node (ref "R9") (pin "2") (pinfunction "2_2") (pintype "passive"))
      (node (ref "TP10") (pin "TP") (pinfunction "TP_TP") (pintype "input"))
      (node (ref "U14") (pin "2") (pinfunction "I1_2") (pintype "input"))
      (node (ref "U16") (pin "8") (pinfunction "V+_8") (pintype "power_in"))
      (node (ref "U3") (pin "1") (pinfunction "VOUT_1") (pintype "output"))
      (node (ref "U4") (pin "4") (pinfunction "V+_4") (pintype "power_in"))
    )
    (net (code "137") (name "VCCIO") (class "Default")
      (node (ref "C24") (pin "1") (pinfunction "1_1") (pintype "passive"))
      (node (ref "C27") (pin "1") (pinfunction "1_1") (pintype "passive"))
      (node (ref "D4") (pin "C") (pinfunction "C_C") (pintype "passive"))
      (node (ref "D6") (pin "C") (pinfunction "C_C") (pintype "passive"))
      (node (ref "J1") (pin "1") (pinfunction "1_1") (pintype "passive"))
      (node (ref "R41") (pin "2") (pinfunction "2_2") (pintype "passive"))
      (node (ref "TP9") (pin "TP") (pinfunction "TP_TP") (pintype "input"))
      (node (ref "U10") (pin "14") (pinfunction "VDD_14") (pintype "power_in"))
      (node (ref "U10") (pin "9") (pinfunction "I_9") (pintype "input"))
      (node (ref "U12") (pin "14") (pinfunction "VCC_14") (pintype "power_in"))
      (node (ref "U13") (pin "6") (pinfunction "VDD_6") (pintype "power_in"))
      (node (ref "U14") (pin "14") (pinfunction "VCC_14") (pintype "power_in"))
      (node (ref "U15") (pin "16") (pinfunction "VCC_16") (pintype "power_in"))
      (node (ref "U17") (pin "8") (pinfunction "V+_8") (pintype "power_in"))
      (node (ref "U18") (pin "14") (pinfunction "VCC_14") (pintype "power_in"))
    )
    (net (code "138") (name "VIN") (class "Default")
      (node (ref "D18") (pin "A") (pinfunction "A_A") (pintype "passive"))
      (node (ref "D2") (pin "A") (pinfunction "A_A") (pintype "passive"))
      (node (ref "Q1") (pin "1") (pinfunction "G_1") (pintype "bidirectional"))
      (node (ref "R2") (pin "2") (pinfunction "2_2") (pintype "passive"))
      (node (ref "R45") (pin "1") (pinfunction "1_1") (pintype "passive"))
      (node (ref "R74") (pin "1") (pinfunction "1_1") (pintype "passive"))
      (node (ref "R8") (pin "2") (pinfunction "2_2") (pintype "passive"))
    )
    (net (code "139") (name "VINCHG") (class "Default")
      (node (ref "C15") (pin "+") (pinfunction "+_+") (pintype "passive"))
      (node (ref "D18") (pin "C") (pinfunction "C_C") (pintype "passive"))
      (node (ref "U7") (pin "1") (pinfunction "IN_1") (pintype "input"))
    )
    (net (code "140") (name "VINH") (class "Default")
      (node (ref "F2") (pin "2") (pinfunction "2_2") (pintype "passive"))
      (node (ref "R44") (pin "1") (pinfunction "1_1") (pintype "passive"))
      (node (ref "R8") (pin "1") (pinfunction "1_1") (pintype "passive"))
    )
    (net (code "141") (name "^CHG_CTRL") (class "Default")
      (node (ref "U13") (pin "17") (pinfunction "PE5/SPI_NSS_17") (pintype "bidirectional"))
      (node (ref "U7") (pin "5") (pinfunction "EN_5") (pintype "input"))
    )
    (net (code "142") (name "^HDDON") (class "Default")
      (node (ref "C29") (pin "1") (pinfunction "1_1") (pintype "passive"))
      (node (ref "S3") (pin "2") (pinfunction "P_2") (pintype "passive"))
      (node (ref "U13") (pin "2") (pinfunction "PA1/OSCIN_2") (pintype "bidirectional"))
    )
    (net (code "143") (name "^PRI_CTRL") (class "Default")
      (node (ref "U1") (pin "5") (pinfunction "EN_5") (pintype "input"))
      (node (ref "U10") (pin "10") (pinfunction "O_10") (pintype "output"))
    )
    (net (code "144") (name "^PWRON") (class "Default")
      (node (ref "C28") (pin "1") (pinfunction "1_1") (pintype "passive"))
      (node (ref "S1") (pin "2") (pinfunction "P_2") (pintype "passive"))
      (node (ref "U13") (pin "32") (pinfunction "PD7/TLI[TIM1_CH4]_32") (pintype "bidirectional"))
    )
    (net (code "145") (name "unconnected-(S1-S-Pad3)") (class "Default")
      (node (ref "S1") (pin "3") (pinfunction "S_3") (pintype "passive"))
    )
    (net (code "146") (name "unconnected-(S3-O-Pad1)") (class "Default")
      (node (ref "S3") (pin "1") (pinfunction "O_1") (pintype "passive"))
    )
    (net (code "147") (name "unconnected-(U9-STDBY-Pad6)") (class "Default")
      (node (ref "U9") (pin "6") (pinfunction "STDBY_6") (pintype "bidirectional"))
    )
    (net (code "148") (name "unconnected-(U10C-O-Pad6)") (class "Default")
      (node (ref "U10") (pin "6") (pinfunction "O_6") (pintype "output"))
    )
    (net (code "149") (name "unconnected-(U10D-O-Pad8)") (class "Default")
      (node (ref "U10") (pin "8") (pinfunction "O_8") (pintype "output"))
    )
    (net (code "150") (name "unconnected-(U13-PB5{slash}I2C_SDA-Pad11)") (class "Default")
      (node (ref "U13") (pin "11") (pinfunction "PB5/I2C_SDA_11") (pintype "bidirectional"))
    )
    (net (code "151") (name "unconnected-(U18A-O-Pad3)") (class "Default")
      (node (ref "U18") (pin "3") (pinfunction "O_3") (pintype "output"))
    )
    (net (code "152") (name "unconnected-(U18B-O-Pad6)") (class "Default")
      (node (ref "U18") (pin "6") (pinfunction "O_6") (pintype "output"))
    )
    (net (code "153") (name "unconnected-(U18D-O-Pad11)") (class "Default")
      (node (ref "U18") (pin "11") (pinfunction "O_11") (pintype "output"))
    )
  )
)
